# PowerBoard.net
KiCad netlist of a schematic drawn in EAGLE
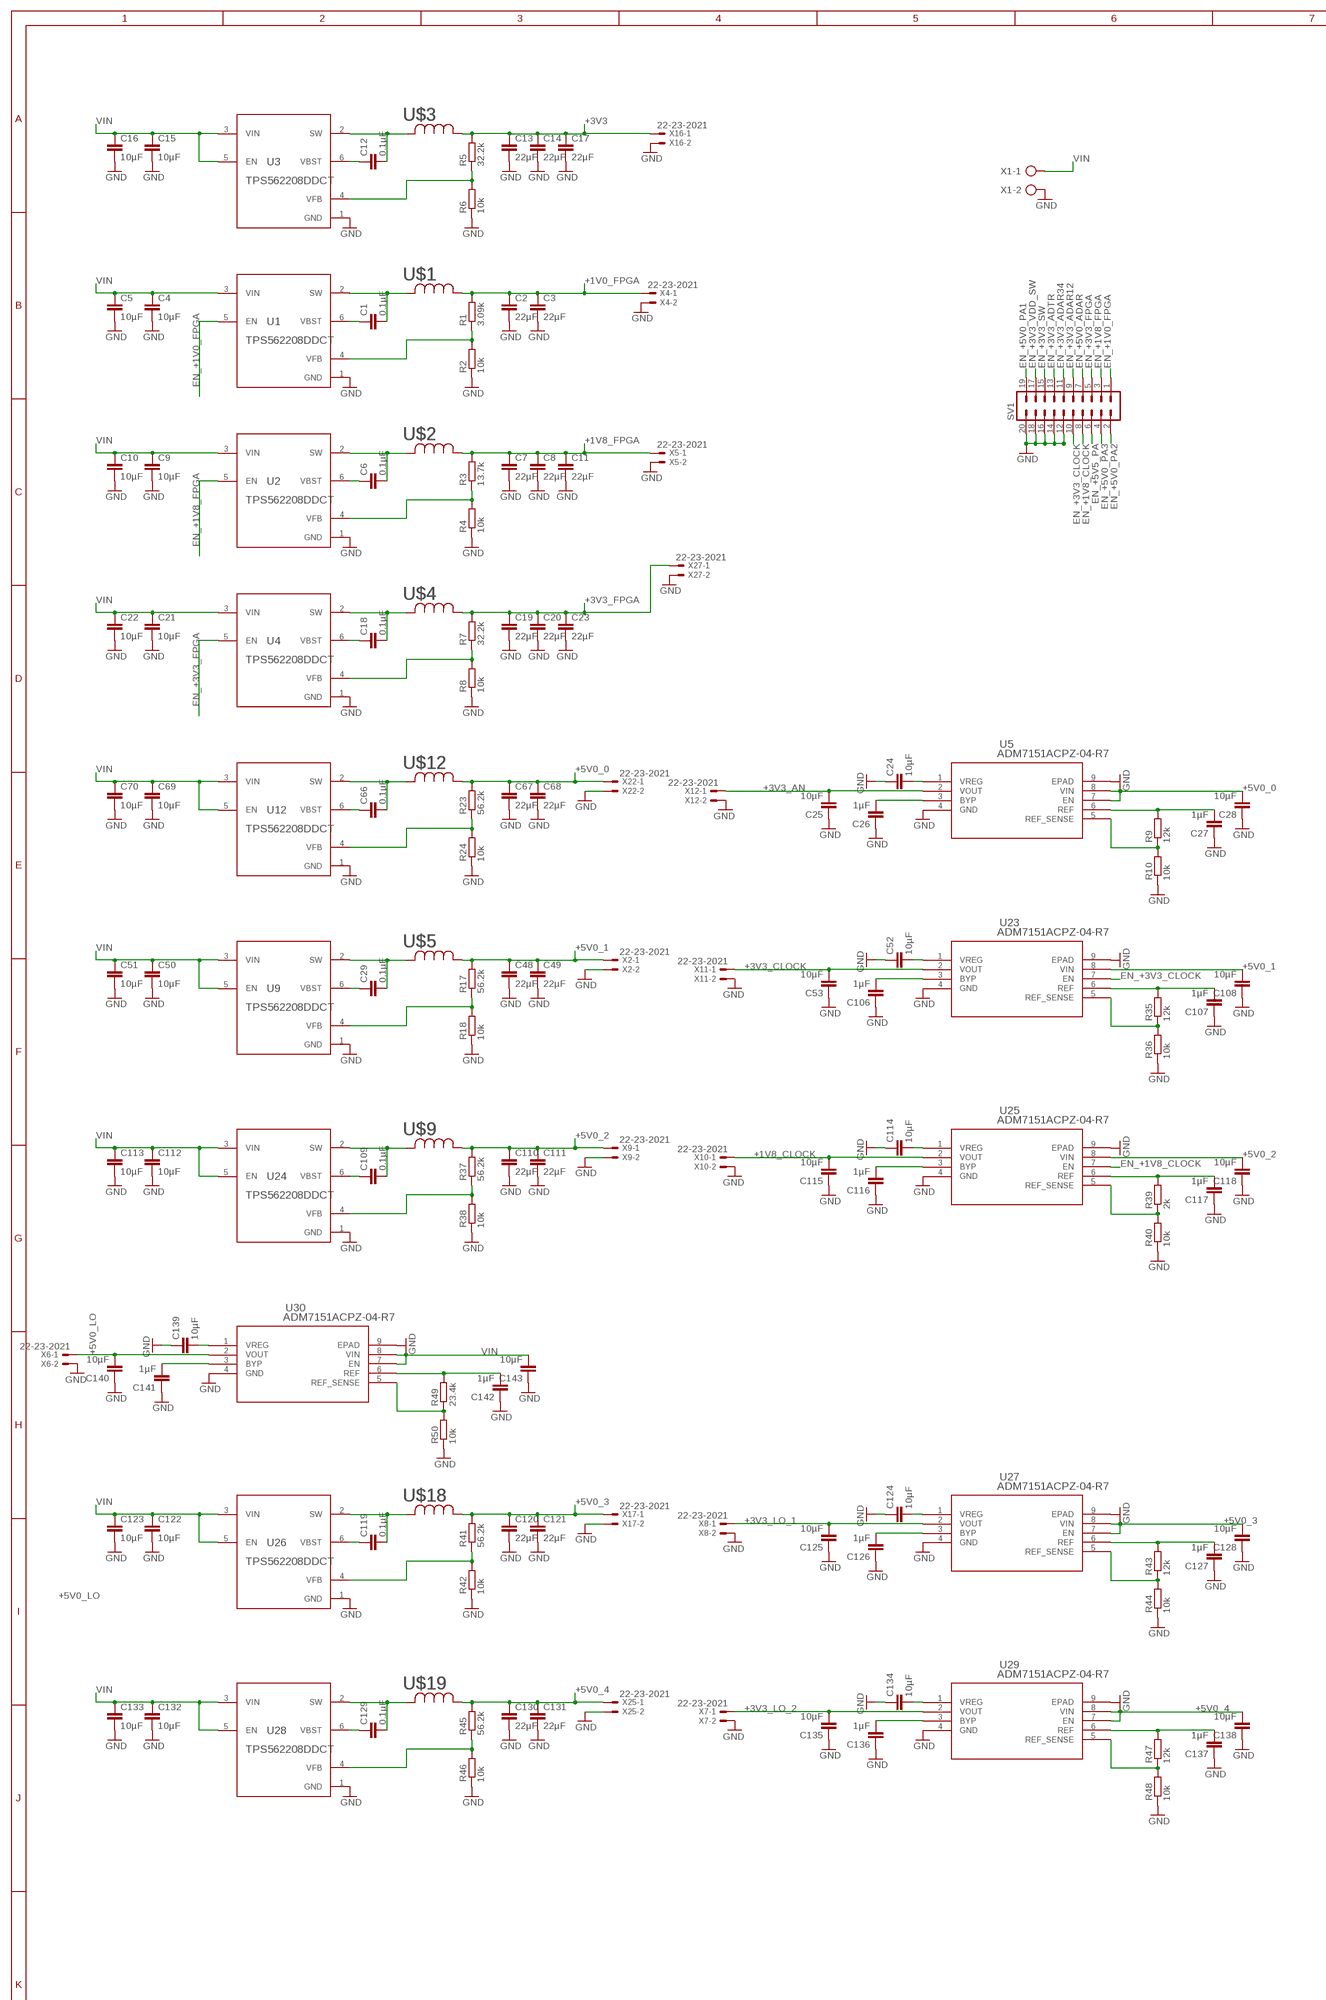
[diagram p0: schematic, sheet 1, part 1 of 3]
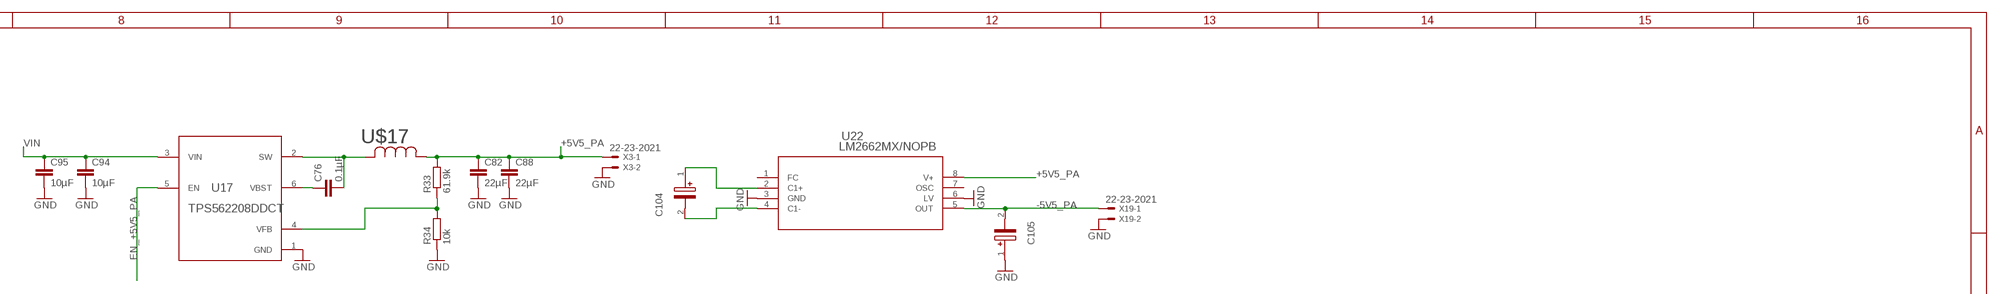
[diagram p1: schematic, sheet 1, part 2 of 3]
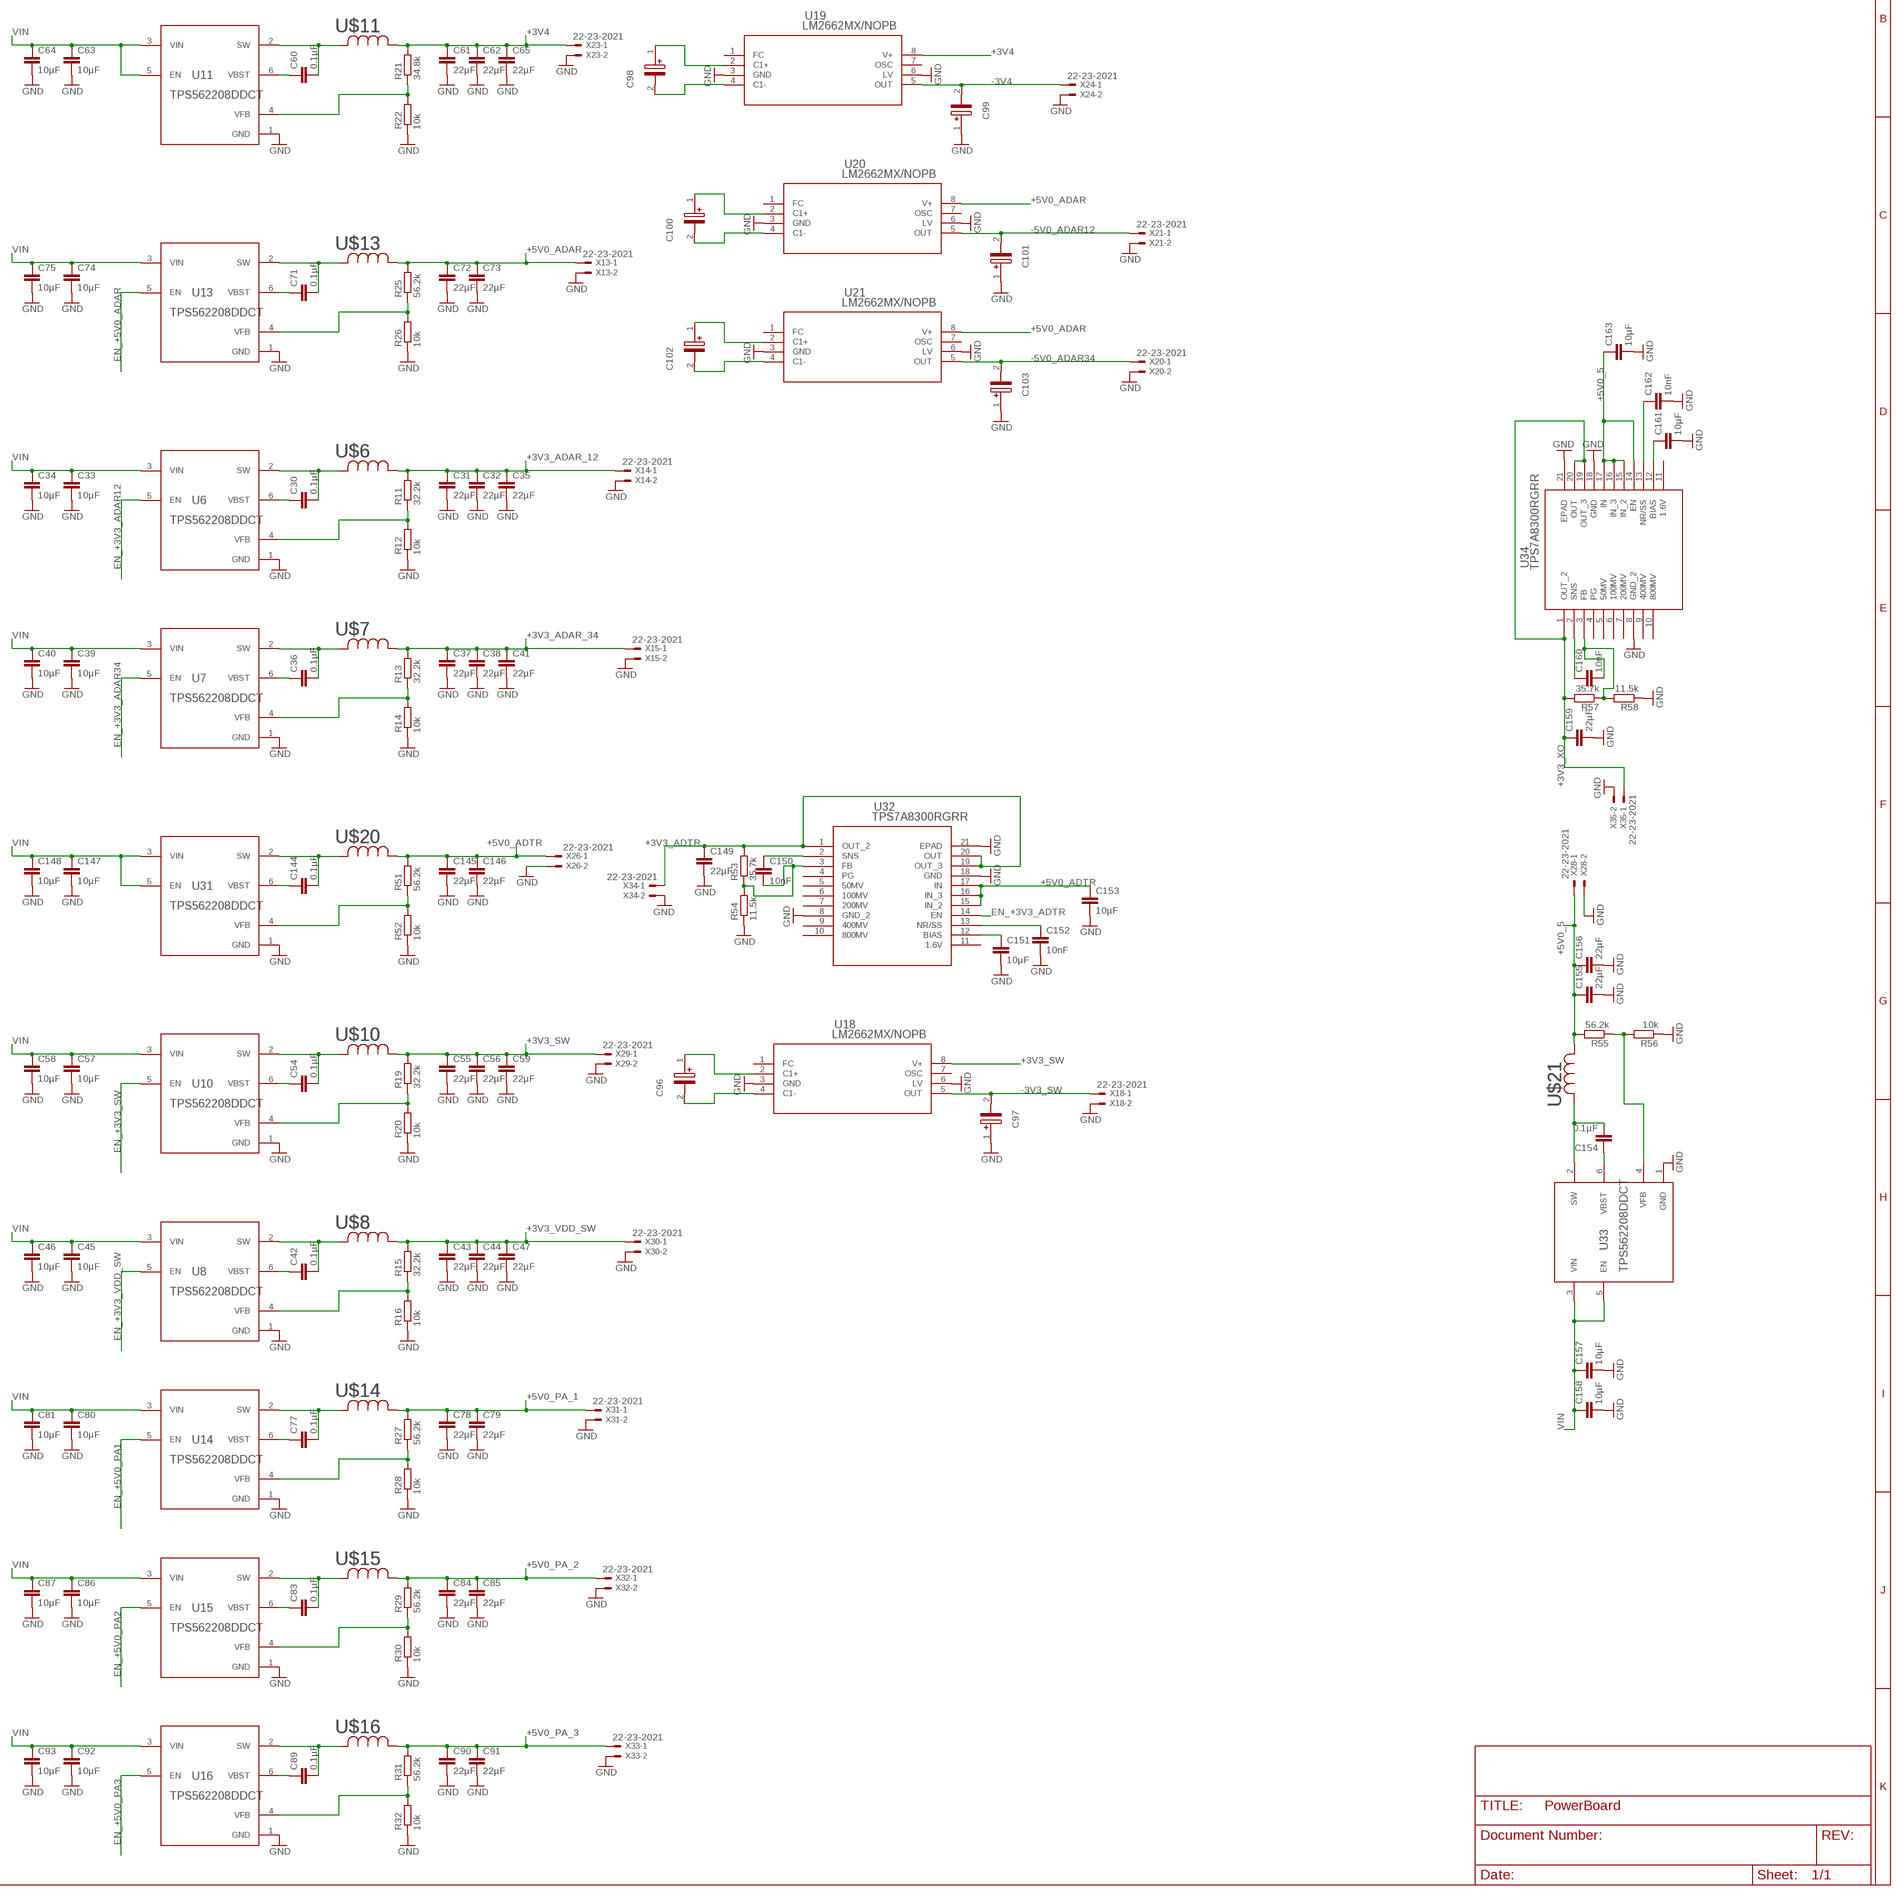
[diagram p2: schematic, sheet 1, part 3 of 3]

(export (version "E")
  (design (tool "Eeschema 10.0.6"))
  (components
    (comp (ref "C1")
      (value "0.1µF")
      (footprint "eagle-import:C0805")
      (libsource (lib "eagle-import") (part "C-EUC0805"))
    )
    (comp (ref "C2")
      (value "22µF")
      (footprint "eagle-import:C0603")
      (libsource (lib "eagle-import") (part "C-EUC0603"))
    )
    (comp (ref "C3")
      (value "22µF")
      (footprint "eagle-import:C0603")
      (libsource (lib "eagle-import") (part "C-EUC0603"))
    )
    (comp (ref "C4")
      (value "10µF")
      (footprint "eagle-import:C0805")
      (libsource (lib "eagle-import") (part "C-EUC0805"))
    )
    (comp (ref "C5")
      (value "10µF")
      (footprint "eagle-import:C0805")
      (libsource (lib "eagle-import") (part "C-EUC0805"))
    )
    (comp (ref "C6")
      (value "0.1µF")
      (footprint "eagle-import:C0805")
      (libsource (lib "eagle-import") (part "C-EUC0805"))
    )
    (comp (ref "C7")
      (value "22µF")
      (footprint "eagle-import:C0603")
      (libsource (lib "eagle-import") (part "C-EUC0603"))
    )
    (comp (ref "C8")
      (value "22µF")
      (footprint "eagle-import:C0603")
      (libsource (lib "eagle-import") (part "C-EUC0603"))
    )
    (comp (ref "C9")
      (value "10µF")
      (footprint "eagle-import:C0805")
      (libsource (lib "eagle-import") (part "C-EUC0805"))
    )
    (comp (ref "C10")
      (value "10µF")
      (footprint "eagle-import:C0805")
      (libsource (lib "eagle-import") (part "C-EUC0805"))
    )
    (comp (ref "C11")
      (value "22µF")
      (footprint "eagle-import:C0603")
      (libsource (lib "eagle-import") (part "C-EUC0603"))
    )
    (comp (ref "C12")
      (value "0.1µF")
      (footprint "eagle-import:C0805")
      (libsource (lib "eagle-import") (part "C-EUC0805"))
    )
    (comp (ref "C13")
      (value "22µF")
      (footprint "eagle-import:C0603")
      (libsource (lib "eagle-import") (part "C-EUC0603"))
    )
    (comp (ref "C14")
      (value "22µF")
      (footprint "eagle-import:C0603")
      (libsource (lib "eagle-import") (part "C-EUC0603"))
    )
    (comp (ref "C15")
      (value "10µF")
      (footprint "eagle-import:C0805")
      (libsource (lib "eagle-import") (part "C-EUC0805"))
    )
    (comp (ref "C16")
      (value "10µF")
      (footprint "eagle-import:C0805")
      (libsource (lib "eagle-import") (part "C-EUC0805"))
    )
    (comp (ref "C17")
      (value "22µF")
      (footprint "eagle-import:C0603")
      (libsource (lib "eagle-import") (part "C-EUC0603"))
    )
    (comp (ref "C18")
      (value "0.1µF")
      (footprint "eagle-import:C0805")
      (libsource (lib "eagle-import") (part "C-EUC0805"))
    )
    (comp (ref "C19")
      (value "22µF")
      (footprint "eagle-import:C0603")
      (libsource (lib "eagle-import") (part "C-EUC0603"))
    )
    (comp (ref "C20")
      (value "22µF")
      (footprint "eagle-import:C0603")
      (libsource (lib "eagle-import") (part "C-EUC0603"))
    )
    (comp (ref "C21")
      (value "10µF")
      (footprint "eagle-import:C0805")
      (libsource (lib "eagle-import") (part "C-EUC0805"))
    )
    (comp (ref "C22")
      (value "10µF")
      (footprint "eagle-import:C0805")
      (libsource (lib "eagle-import") (part "C-EUC0805"))
    )
    (comp (ref "C23")
      (value "22µF")
      (footprint "eagle-import:C0603")
      (libsource (lib "eagle-import") (part "C-EUC0603"))
    )
    (comp (ref "C24")
      (value "10µF")
      (footprint "eagle-import:C0805")
      (libsource (lib "eagle-import") (part "C-EUC0805"))
    )
    (comp (ref "C25")
      (value "10µF")
      (footprint "eagle-import:C0805")
      (libsource (lib "eagle-import") (part "C-EUC0805"))
    )
    (comp (ref "C26")
      (value "1µF")
      (footprint "eagle-import:C0805")
      (libsource (lib "eagle-import") (part "C-EUC0805"))
    )
    (comp (ref "C27")
      (value "1µF")
      (footprint "eagle-import:C0805")
      (libsource (lib "eagle-import") (part "C-EUC0805"))
    )
    (comp (ref "C28")
      (value "10µF")
      (footprint "eagle-import:C0805")
      (libsource (lib "eagle-import") (part "C-EUC0805"))
    )
    (comp (ref "C29")
      (value "0.1µF")
      (footprint "eagle-import:C0805")
      (libsource (lib "eagle-import") (part "C-EUC0805"))
    )
    (comp (ref "C30")
      (value "0.1µF")
      (footprint "eagle-import:C0805")
      (libsource (lib "eagle-import") (part "C-EUC0805"))
    )
    (comp (ref "C31")
      (value "22µF")
      (footprint "eagle-import:C0603")
      (libsource (lib "eagle-import") (part "C-EUC0603"))
    )
    (comp (ref "C32")
      (value "22µF")
      (footprint "eagle-import:C0603")
      (libsource (lib "eagle-import") (part "C-EUC0603"))
    )
    (comp (ref "C33")
      (value "10µF")
      (footprint "eagle-import:C0805")
      (libsource (lib "eagle-import") (part "C-EUC0805"))
    )
    (comp (ref "C34")
      (value "10µF")
      (footprint "eagle-import:C0805")
      (libsource (lib "eagle-import") (part "C-EUC0805"))
    )
    (comp (ref "C35")
      (value "22µF")
      (footprint "eagle-import:C0603")
      (libsource (lib "eagle-import") (part "C-EUC0603"))
    )
    (comp (ref "C36")
      (value "0.1µF")
      (footprint "eagle-import:C0805")
      (libsource (lib "eagle-import") (part "C-EUC0805"))
    )
    (comp (ref "C37")
      (value "22µF")
      (footprint "eagle-import:C0603")
      (libsource (lib "eagle-import") (part "C-EUC0603"))
    )
    (comp (ref "C38")
      (value "22µF")
      (footprint "eagle-import:C0603")
      (libsource (lib "eagle-import") (part "C-EUC0603"))
    )
    (comp (ref "C39")
      (value "10µF")
      (footprint "eagle-import:C0805")
      (libsource (lib "eagle-import") (part "C-EUC0805"))
    )
    (comp (ref "C40")
      (value "10µF")
      (footprint "eagle-import:C0805")
      (libsource (lib "eagle-import") (part "C-EUC0805"))
    )
    (comp (ref "C41")
      (value "22µF")
      (footprint "eagle-import:C0603")
      (libsource (lib "eagle-import") (part "C-EUC0603"))
    )
    (comp (ref "C42")
      (value "0.1µF")
      (footprint "eagle-import:C0805")
      (libsource (lib "eagle-import") (part "C-EUC0805"))
    )
    (comp (ref "C43")
      (value "22µF")
      (footprint "eagle-import:C0603")
      (libsource (lib "eagle-import") (part "C-EUC0603"))
    )
    (comp (ref "C44")
      (value "22µF")
      (footprint "eagle-import:C0603")
      (libsource (lib "eagle-import") (part "C-EUC0603"))
    )
    (comp (ref "C45")
      (value "10µF")
      (footprint "eagle-import:C0805")
      (libsource (lib "eagle-import") (part "C-EUC0805"))
    )
    (comp (ref "C46")
      (value "10µF")
      (footprint "eagle-import:C0805")
      (libsource (lib "eagle-import") (part "C-EUC0805"))
    )
    (comp (ref "C47")
      (value "22µF")
      (footprint "eagle-import:C0603")
      (libsource (lib "eagle-import") (part "C-EUC0603"))
    )
    (comp (ref "C48")
      (value "22µF")
      (footprint "eagle-import:C0603")
      (libsource (lib "eagle-import") (part "C-EUC0603"))
    )
    (comp (ref "C49")
      (value "22µF")
      (footprint "eagle-import:C0603")
      (libsource (lib "eagle-import") (part "C-EUC0603"))
    )
    (comp (ref "C50")
      (value "10µF")
      (footprint "eagle-import:C0805")
      (libsource (lib "eagle-import") (part "C-EUC0805"))
    )
    (comp (ref "C51")
      (value "10µF")
      (footprint "eagle-import:C0805")
      (libsource (lib "eagle-import") (part "C-EUC0805"))
    )
    (comp (ref "C52")
      (value "10µF")
      (footprint "eagle-import:C0805")
      (libsource (lib "eagle-import") (part "C-EUC0805"))
    )
    (comp (ref "C53")
      (value "10µF")
      (footprint "eagle-import:C0805")
      (libsource (lib "eagle-import") (part "C-EUC0805"))
    )
    (comp (ref "C54")
      (value "0.1µF")
      (footprint "eagle-import:C0805")
      (libsource (lib "eagle-import") (part "C-EUC0805"))
    )
    (comp (ref "C55")
      (value "22µF")
      (footprint "eagle-import:C0603")
      (libsource (lib "eagle-import") (part "C-EUC0603"))
    )
    (comp (ref "C56")
      (value "22µF")
      (footprint "eagle-import:C0603")
      (libsource (lib "eagle-import") (part "C-EUC0603"))
    )
    (comp (ref "C57")
      (value "10µF")
      (footprint "eagle-import:C0805")
      (libsource (lib "eagle-import") (part "C-EUC0805"))
    )
    (comp (ref "C58")
      (value "10µF")
      (footprint "eagle-import:C0805")
      (libsource (lib "eagle-import") (part "C-EUC0805"))
    )
    (comp (ref "C59")
      (value "22µF")
      (footprint "eagle-import:C0603")
      (libsource (lib "eagle-import") (part "C-EUC0603"))
    )
    (comp (ref "C60")
      (value "0.1µF")
      (footprint "eagle-import:C0805")
      (libsource (lib "eagle-import") (part "C-EUC0805"))
    )
    (comp (ref "C61")
      (value "22µF")
      (footprint "eagle-import:C0603")
      (libsource (lib "eagle-import") (part "C-EUC0603"))
    )
    (comp (ref "C62")
      (value "22µF")
      (footprint "eagle-import:C0603")
      (libsource (lib "eagle-import") (part "C-EUC0603"))
    )
    (comp (ref "C63")
      (value "10µF")
      (footprint "eagle-import:C0805")
      (libsource (lib "eagle-import") (part "C-EUC0805"))
    )
    (comp (ref "C64")
      (value "10µF")
      (footprint "eagle-import:C0805")
      (libsource (lib "eagle-import") (part "C-EUC0805"))
    )
    (comp (ref "C65")
      (value "22µF")
      (footprint "eagle-import:C0603")
      (libsource (lib "eagle-import") (part "C-EUC0603"))
    )
    (comp (ref "C66")
      (value "0.1µF")
      (footprint "eagle-import:C0805")
      (libsource (lib "eagle-import") (part "C-EUC0805"))
    )
    (comp (ref "C67")
      (value "22µF")
      (footprint "eagle-import:C0603")
      (libsource (lib "eagle-import") (part "C-EUC0603"))
    )
    (comp (ref "C68")
      (value "22µF")
      (footprint "eagle-import:C0603")
      (libsource (lib "eagle-import") (part "C-EUC0603"))
    )
    (comp (ref "C69")
      (value "10µF")
      (footprint "eagle-import:C0805")
      (libsource (lib "eagle-import") (part "C-EUC0805"))
    )
    (comp (ref "C70")
      (value "10µF")
      (footprint "eagle-import:C0805")
      (libsource (lib "eagle-import") (part "C-EUC0805"))
    )
    (comp (ref "C71")
      (value "0.1µF")
      (footprint "eagle-import:C0805")
      (libsource (lib "eagle-import") (part "C-EUC0805"))
    )
    (comp (ref "C72")
      (value "22µF")
      (footprint "eagle-import:C0603")
      (libsource (lib "eagle-import") (part "C-EUC0603"))
    )
    (comp (ref "C73")
      (value "22µF")
      (footprint "eagle-import:C0603")
      (libsource (lib "eagle-import") (part "C-EUC0603"))
    )
    (comp (ref "C74")
      (value "10µF")
      (footprint "eagle-import:C0805")
      (libsource (lib "eagle-import") (part "C-EUC0805"))
    )
    (comp (ref "C75")
      (value "10µF")
      (footprint "eagle-import:C0805")
      (libsource (lib "eagle-import") (part "C-EUC0805"))
    )
    (comp (ref "C76")
      (value "0.1µF")
      (footprint "eagle-import:C0805")
      (libsource (lib "eagle-import") (part "C-EUC0805"))
    )
    (comp (ref "C77")
      (value "0.1µF")
      (footprint "eagle-import:C0805")
      (libsource (lib "eagle-import") (part "C-EUC0805"))
    )
    (comp (ref "C78")
      (value "22µF")
      (footprint "eagle-import:C0603")
      (libsource (lib "eagle-import") (part "C-EUC0603"))
    )
    (comp (ref "C79")
      (value "22µF")
      (footprint "eagle-import:C0603")
      (libsource (lib "eagle-import") (part "C-EUC0603"))
    )
    (comp (ref "C80")
      (value "10µF")
      (footprint "eagle-import:C0805")
      (libsource (lib "eagle-import") (part "C-EUC0805"))
    )
    (comp (ref "C81")
      (value "10µF")
      (footprint "eagle-import:C0805")
      (libsource (lib "eagle-import") (part "C-EUC0805"))
    )
    (comp (ref "C82")
      (value "22µF")
      (footprint "eagle-import:C0603")
      (libsource (lib "eagle-import") (part "C-EUC0603"))
    )
    (comp (ref "C83")
      (value "0.1µF")
      (footprint "eagle-import:C0805")
      (libsource (lib "eagle-import") (part "C-EUC0805"))
    )
    (comp (ref "C84")
      (value "22µF")
      (footprint "eagle-import:C0603")
      (libsource (lib "eagle-import") (part "C-EUC0603"))
    )
    (comp (ref "C85")
      (value "22µF")
      (footprint "eagle-import:C0603")
      (libsource (lib "eagle-import") (part "C-EUC0603"))
    )
    (comp (ref "C86")
      (value "10µF")
      (footprint "eagle-import:C0805")
      (libsource (lib "eagle-import") (part "C-EUC0805"))
    )
    (comp (ref "C87")
      (value "10µF")
      (footprint "eagle-import:C0805")
      (libsource (lib "eagle-import") (part "C-EUC0805"))
    )
    (comp (ref "C88")
      (value "22µF")
      (footprint "eagle-import:C0603")
      (libsource (lib "eagle-import") (part "C-EUC0603"))
    )
    (comp (ref "C89")
      (value "0.1µF")
      (footprint "eagle-import:C0805")
      (libsource (lib "eagle-import") (part "C-EUC0805"))
    )
    (comp (ref "C90")
      (value "22µF")
      (footprint "eagle-import:C0603")
      (libsource (lib "eagle-import") (part "C-EUC0603"))
    )
    (comp (ref "C91")
      (value "22µF")
      (footprint "eagle-import:C0603")
      (libsource (lib "eagle-import") (part "C-EUC0603"))
    )
    (comp (ref "C92")
      (value "10µF")
      (footprint "eagle-import:C0805")
      (libsource (lib "eagle-import") (part "C-EUC0805"))
    )
    (comp (ref "C93")
      (value "10µF")
      (footprint "eagle-import:C0805")
      (libsource (lib "eagle-import") (part "C-EUC0805"))
    )
    (comp (ref "C94")
      (value "10µF")
      (footprint "eagle-import:C0805")
      (libsource (lib "eagle-import") (part "C-EUC0805"))
    )
    (comp (ref "C95")
      (value "10µF")
      (footprint "eagle-import:C0805")
      (libsource (lib "eagle-import") (part "C-EUC0805"))
    )
    (comp (ref "C96")
      (value "T521W476M020ATE045")
      (footprint "eagle-import:T521W")
      (fields (field (name "MOUSER_PART_NUMBER") "80-T521W476M20ATE045"))
      (libsource (lib "eagle-import") (part "T521W476M020ATE045"))
    )
    (comp (ref "C97")
      (value "T521W476M020ATE045")
      (footprint "eagle-import:T521W")
      (fields (field (name "MOUSER_PART_NUMBER") "80-T521W476M20ATE045"))
      (libsource (lib "eagle-import") (part "T521W476M020ATE045"))
    )
    (comp (ref "C98")
      (value "T521W476M020ATE045")
      (footprint "eagle-import:T521W")
      (fields (field (name "MOUSER_PART_NUMBER") "80-T521W476M20ATE045"))
      (libsource (lib "eagle-import") (part "T521W476M020ATE045"))
    )
    (comp (ref "C99")
      (value "T521W476M020ATE045")
      (footprint "eagle-import:T521W")
      (fields (field (name "MOUSER_PART_NUMBER") "80-T521W476M20ATE045"))
      (libsource (lib "eagle-import") (part "T521W476M020ATE045"))
    )
    (comp (ref "C100")
      (value "T521W476M020ATE045")
      (footprint "eagle-import:T521W")
      (fields (field (name "MOUSER_PART_NUMBER") "80-T521W476M20ATE045"))
      (libsource (lib "eagle-import") (part "T521W476M020ATE045"))
    )
    (comp (ref "C101")
      (value "T521W476M020ATE045")
      (footprint "eagle-import:T521W")
      (fields (field (name "MOUSER_PART_NUMBER") "80-T521W476M20ATE045"))
      (libsource (lib "eagle-import") (part "T521W476M020ATE045"))
    )
    (comp (ref "C102")
      (value "T521W476M020ATE045")
      (footprint "eagle-import:T521W")
      (fields (field (name "MOUSER_PART_NUMBER") "80-T521W476M20ATE045"))
      (libsource (lib "eagle-import") (part "T521W476M020ATE045"))
    )
    (comp (ref "C103")
      (value "T521W476M020ATE045")
      (footprint "eagle-import:T521W")
      (fields (field (name "MOUSER_PART_NUMBER") "80-T521W476M20ATE045"))
      (libsource (lib "eagle-import") (part "T521W476M020ATE045"))
    )
    (comp (ref "C104")
      (value "T521W476M020ATE045")
      (footprint "eagle-import:T521W")
      (fields (field (name "MOUSER_PART_NUMBER") "80-T521W476M20ATE045"))
      (libsource (lib "eagle-import") (part "T521W476M020ATE045"))
    )
    (comp (ref "C105")
      (value "T521W476M020ATE045")
      (footprint "eagle-import:T521W")
      (fields (field (name "MOUSER_PART_NUMBER") "80-T521W476M20ATE045"))
      (libsource (lib "eagle-import") (part "T521W476M020ATE045"))
    )
    (comp (ref "C106")
      (value "1µF")
      (footprint "eagle-import:C0805")
      (libsource (lib "eagle-import") (part "C-EUC0805"))
    )
    (comp (ref "C107")
      (value "1µF")
      (footprint "eagle-import:C0805")
      (libsource (lib "eagle-import") (part "C-EUC0805"))
    )
    (comp (ref "C108")
      (value "10µF")
      (footprint "eagle-import:C0805")
      (libsource (lib "eagle-import") (part "C-EUC0805"))
    )
    (comp (ref "C109")
      (value "0.1µF")
      (footprint "eagle-import:C0805")
      (libsource (lib "eagle-import") (part "C-EUC0805"))
    )
    (comp (ref "C110")
      (value "22µF")
      (footprint "eagle-import:C0603")
      (libsource (lib "eagle-import") (part "C-EUC0603"))
    )
    (comp (ref "C111")
      (value "22µF")
      (footprint "eagle-import:C0603")
      (libsource (lib "eagle-import") (part "C-EUC0603"))
    )
    (comp (ref "C112")
      (value "10µF")
      (footprint "eagle-import:C0805")
      (libsource (lib "eagle-import") (part "C-EUC0805"))
    )
    (comp (ref "C113")
      (value "10µF")
      (footprint "eagle-import:C0805")
      (libsource (lib "eagle-import") (part "C-EUC0805"))
    )
    (comp (ref "C114")
      (value "10µF")
      (footprint "eagle-import:C0805")
      (libsource (lib "eagle-import") (part "C-EUC0805"))
    )
    (comp (ref "C115")
      (value "10µF")
      (footprint "eagle-import:C0805")
      (libsource (lib "eagle-import") (part "C-EUC0805"))
    )
    (comp (ref "C116")
      (value "1µF")
      (footprint "eagle-import:C0805")
      (libsource (lib "eagle-import") (part "C-EUC0805"))
    )
    (comp (ref "C117")
      (value "1µF")
      (footprint "eagle-import:C0805")
      (libsource (lib "eagle-import") (part "C-EUC0805"))
    )
    (comp (ref "C118")
      (value "10µF")
      (footprint "eagle-import:C0805")
      (libsource (lib "eagle-import") (part "C-EUC0805"))
    )
    (comp (ref "C119")
      (value "0.1µF")
      (footprint "eagle-import:C0805")
      (libsource (lib "eagle-import") (part "C-EUC0805"))
    )
    (comp (ref "C120")
      (value "22µF")
      (footprint "eagle-import:C0603")
      (libsource (lib "eagle-import") (part "C-EUC0603"))
    )
    (comp (ref "C121")
      (value "22µF")
      (footprint "eagle-import:C0603")
      (libsource (lib "eagle-import") (part "C-EUC0603"))
    )
    (comp (ref "C122")
      (value "10µF")
      (footprint "eagle-import:C0805")
      (libsource (lib "eagle-import") (part "C-EUC0805"))
    )
    (comp (ref "C123")
      (value "10µF")
      (footprint "eagle-import:C0805")
      (libsource (lib "eagle-import") (part "C-EUC0805"))
    )
    (comp (ref "C124")
      (value "10µF")
      (footprint "eagle-import:C0805")
      (libsource (lib "eagle-import") (part "C-EUC0805"))
    )
    (comp (ref "C125")
      (value "10µF")
      (footprint "eagle-import:C0805")
      (libsource (lib "eagle-import") (part "C-EUC0805"))
    )
    (comp (ref "C126")
      (value "1µF")
      (footprint "eagle-import:C0805")
      (libsource (lib "eagle-import") (part "C-EUC0805"))
    )
    (comp (ref "C127")
      (value "1µF")
      (footprint "eagle-import:C0805")
      (libsource (lib "eagle-import") (part "C-EUC0805"))
    )
    (comp (ref "C128")
      (value "10µF")
      (footprint "eagle-import:C0805")
      (libsource (lib "eagle-import") (part "C-EUC0805"))
    )
    (comp (ref "C129")
      (value "0.1µF")
      (footprint "eagle-import:C0805")
      (libsource (lib "eagle-import") (part "C-EUC0805"))
    )
    (comp (ref "C130")
      (value "22µF")
      (footprint "eagle-import:C0603")
      (libsource (lib "eagle-import") (part "C-EUC0603"))
    )
    (comp (ref "C131")
      (value "22µF")
      (footprint "eagle-import:C0603")
      (libsource (lib "eagle-import") (part "C-EUC0603"))
    )
    (comp (ref "C132")
      (value "10µF")
      (footprint "eagle-import:C0805")
      (libsource (lib "eagle-import") (part "C-EUC0805"))
    )
    (comp (ref "C133")
      (value "10µF")
      (footprint "eagle-import:C0805")
      (libsource (lib "eagle-import") (part "C-EUC0805"))
    )
    (comp (ref "C134")
      (value "10µF")
      (footprint "eagle-import:C0805")
      (libsource (lib "eagle-import") (part "C-EUC0805"))
    )
    (comp (ref "C135")
      (value "10µF")
      (footprint "eagle-import:C0805")
      (libsource (lib "eagle-import") (part "C-EUC0805"))
    )
    (comp (ref "C136")
      (value "1µF")
      (footprint "eagle-import:C0805")
      (libsource (lib "eagle-import") (part "C-EUC0805"))
    )
    (comp (ref "C137")
      (value "1µF")
      (footprint "eagle-import:C0805")
      (libsource (lib "eagle-import") (part "C-EUC0805"))
    )
    (comp (ref "C138")
      (value "10µF")
      (footprint "eagle-import:C0805")
      (libsource (lib "eagle-import") (part "C-EUC0805"))
    )
    (comp (ref "C139")
      (value "10µF")
      (footprint "eagle-import:C0805")
      (libsource (lib "eagle-import") (part "C-EUC0805"))
    )
    (comp (ref "C140")
      (value "10µF")
      (footprint "eagle-import:C0805")
      (libsource (lib "eagle-import") (part "C-EUC0805"))
    )
    (comp (ref "C141")
      (value "1µF")
      (footprint "eagle-import:C0805")
      (libsource (lib "eagle-import") (part "C-EUC0805"))
    )
    (comp (ref "C142")
      (value "1µF")
      (footprint "eagle-import:C0805")
      (libsource (lib "eagle-import") (part "C-EUC0805"))
    )
    (comp (ref "C143")
      (value "10µF")
      (footprint "eagle-import:C0805")
      (libsource (lib "eagle-import") (part "C-EUC0805"))
    )
    (comp (ref "C144")
      (value "0.1µF")
      (footprint "eagle-import:C0805")
      (libsource (lib "eagle-import") (part "C-EUC0805"))
    )
    (comp (ref "C145")
      (value "22µF")
      (footprint "eagle-import:C0603")
      (libsource (lib "eagle-import") (part "C-EUC0603"))
    )
    (comp (ref "C146")
      (value "22µF")
      (footprint "eagle-import:C0603")
      (libsource (lib "eagle-import") (part "C-EUC0603"))
    )
    (comp (ref "C147")
      (value "10µF")
      (footprint "eagle-import:C0805")
      (libsource (lib "eagle-import") (part "C-EUC0805"))
    )
    (comp (ref "C148")
      (value "10µF")
      (footprint "eagle-import:C0805")
      (libsource (lib "eagle-import") (part "C-EUC0805"))
    )
    (comp (ref "C149")
      (value "22µF")
      (footprint "eagle-import:C0603")
      (libsource (lib "eagle-import") (part "C-EUC0603"))
    )
    (comp (ref "C150")
      (value "10nF")
      (footprint "eagle-import:C0603")
      (libsource (lib "eagle-import") (part "C-EUC0603"))
    )
    (comp (ref "C151")
      (value "10µF")
      (footprint "eagle-import:C0603")
      (libsource (lib "eagle-import") (part "C-EUC0603"))
    )
    (comp (ref "C152")
      (value "10nF")
      (footprint "eagle-import:C0603")
      (libsource (lib "eagle-import") (part "C-EUC0603"))
    )
    (comp (ref "C153")
      (value "10µF")
      (footprint "eagle-import:C0603")
      (libsource (lib "eagle-import") (part "C-EUC0603"))
    )
    (comp (ref "C154")
      (value "0.1µF")
      (footprint "eagle-import:C0805")
      (libsource (lib "eagle-import") (part "C-EUC0805"))
    )
    (comp (ref "C155")
      (value "22µF")
      (footprint "eagle-import:C0603")
      (libsource (lib "eagle-import") (part "C-EUC0603"))
    )
    (comp (ref "C156")
      (value "22µF")
      (footprint "eagle-import:C0603")
      (libsource (lib "eagle-import") (part "C-EUC0603"))
    )
    (comp (ref "C157")
      (value "10µF")
      (footprint "eagle-import:C0805")
      (libsource (lib "eagle-import") (part "C-EUC0805"))
    )
    (comp (ref "C158")
      (value "10µF")
      (footprint "eagle-import:C0805")
      (libsource (lib "eagle-import") (part "C-EUC0805"))
    )
    (comp (ref "C159")
      (value "22µF")
      (footprint "eagle-import:C0603")
      (libsource (lib "eagle-import") (part "C-EUC0603"))
    )
    (comp (ref "C160")
      (value "10nF")
      (footprint "eagle-import:C0603")
      (libsource (lib "eagle-import") (part "C-EUC0603"))
    )
    (comp (ref "C161")
      (value "10µF")
      (footprint "eagle-import:C0603")
      (libsource (lib "eagle-import") (part "C-EUC0603"))
    )
    (comp (ref "C162")
      (value "10nF")
      (footprint "eagle-import:C0603")
      (libsource (lib "eagle-import") (part "C-EUC0603"))
    )
    (comp (ref "C163")
      (value "10µF")
      (footprint "eagle-import:C0603")
      (libsource (lib "eagle-import") (part "C-EUC0603"))
    )
    (comp (ref "R1")
      (value "3.09k")
      (footprint "eagle-import:M0805")
      (libsource (lib "eagle-import") (part "R-EU_M0805"))
    )
    (comp (ref "R2")
      (value "10k")
      (footprint "eagle-import:M0805")
      (libsource (lib "eagle-import") (part "R-EU_M0805"))
    )
    (comp (ref "R3")
      (value "13.7k")
      (footprint "eagle-import:M0805")
      (libsource (lib "eagle-import") (part "R-EU_M0805"))
    )
    (comp (ref "R4")
      (value "10k")
      (footprint "eagle-import:M0805")
      (libsource (lib "eagle-import") (part "R-EU_M0805"))
    )
    (comp (ref "R5")
      (value "32.2k")
      (footprint "eagle-import:M0805")
      (libsource (lib "eagle-import") (part "R-EU_M0805"))
    )
    (comp (ref "R6")
      (value "10k")
      (footprint "eagle-import:M0805")
      (libsource (lib "eagle-import") (part "R-EU_M0805"))
    )
    (comp (ref "R7")
      (value "32.2k")
      (footprint "eagle-import:M0805")
      (libsource (lib "eagle-import") (part "R-EU_M0805"))
    )
    (comp (ref "R8")
      (value "10k")
      (footprint "eagle-import:M0805")
      (libsource (lib "eagle-import") (part "R-EU_M0805"))
    )
    (comp (ref "R9")
      (value "12k")
      (footprint "eagle-import:M0805")
      (libsource (lib "eagle-import") (part "R-EU_M0805"))
    )
    (comp (ref "R10")
      (value "10k")
      (footprint "eagle-import:M0805")
      (libsource (lib "eagle-import") (part "R-EU_M0805"))
    )
    (comp (ref "R11")
      (value "32.2k")
      (footprint "eagle-import:M0805")
      (libsource (lib "eagle-import") (part "R-EU_M0805"))
    )
    (comp (ref "R12")
      (value "10k")
      (footprint "eagle-import:M0805")
      (libsource (lib "eagle-import") (part "R-EU_M0805"))
    )
    (comp (ref "R13")
      (value "32.2k")
      (footprint "eagle-import:M0805")
      (libsource (lib "eagle-import") (part "R-EU_M0805"))
    )
    (comp (ref "R14")
      (value "10k")
      (footprint "eagle-import:M0805")
      (libsource (lib "eagle-import") (part "R-EU_M0805"))
    )
    (comp (ref "R15")
      (value "32.2k")
      (footprint "eagle-import:M0805")
      (libsource (lib "eagle-import") (part "R-EU_M0805"))
    )
    (comp (ref "R16")
      (value "10k")
      (footprint "eagle-import:M0805")
      (libsource (lib "eagle-import") (part "R-EU_M0805"))
    )
    (comp (ref "R17")
      (value "56.2k")
      (footprint "eagle-import:M0805")
      (libsource (lib "eagle-import") (part "R-EU_M0805"))
    )
    (comp (ref "R18")
      (value "10k")
      (footprint "eagle-import:M0805")
      (libsource (lib "eagle-import") (part "R-EU_M0805"))
    )
    (comp (ref "R19")
      (value "32.2k")
      (footprint "eagle-import:M0805")
      (libsource (lib "eagle-import") (part "R-EU_M0805"))
    )
    (comp (ref "R20")
      (value "10k")
      (footprint "eagle-import:M0805")
      (libsource (lib "eagle-import") (part "R-EU_M0805"))
    )
    (comp (ref "R21")
      (value "34.8k")
      (footprint "eagle-import:M0805")
      (libsource (lib "eagle-import") (part "R-EU_M0805"))
    )
    (comp (ref "R22")
      (value "10k")
      (footprint "eagle-import:M0805")
      (libsource (lib "eagle-import") (part "R-EU_M0805"))
    )
    (comp (ref "R23")
      (value "56.2k")
      (footprint "eagle-import:M0805")
      (libsource (lib "eagle-import") (part "R-EU_M0805"))
    )
    (comp (ref "R24")
      (value "10k")
      (footprint "eagle-import:M0805")
      (libsource (lib "eagle-import") (part "R-EU_M0805"))
    )
    (comp (ref "R25")
      (value "56.2k")
      (footprint "eagle-import:M0805")
      (libsource (lib "eagle-import") (part "R-EU_M0805"))
    )
    (comp (ref "R26")
      (value "10k")
      (footprint "eagle-import:M0805")
      (libsource (lib "eagle-import") (part "R-EU_M0805"))
    )
    (comp (ref "R27")
      (value "56.2k")
      (footprint "eagle-import:M0805")
      (libsource (lib "eagle-import") (part "R-EU_M0805"))
    )
    (comp (ref "R28")
      (value "10k")
      (footprint "eagle-import:M0805")
      (libsource (lib "eagle-import") (part "R-EU_M0805"))
    )
    (comp (ref "R29")
      (value "56.2k")
      (footprint "eagle-import:M0805")
      (libsource (lib "eagle-import") (part "R-EU_M0805"))
    )
    (comp (ref "R30")
      (value "10k")
      (footprint "eagle-import:M0805")
      (libsource (lib "eagle-import") (part "R-EU_M0805"))
    )
    (comp (ref "R31")
      (value "56.2k")
      (footprint "eagle-import:M0805")
      (libsource (lib "eagle-import") (part "R-EU_M0805"))
    )
    (comp (ref "R32")
      (value "10k")
      (footprint "eagle-import:M0805")
      (libsource (lib "eagle-import") (part "R-EU_M0805"))
    )
    (comp (ref "R33")
      (value "61.9k")
      (footprint "eagle-import:M0805")
      (libsource (lib "eagle-import") (part "R-EU_M0805"))
    )
    (comp (ref "R34")
      (value "10k")
      (footprint "eagle-import:M0805")
      (libsource (lib "eagle-import") (part "R-EU_M0805"))
    )
    (comp (ref "R35")
      (value "12k")
      (footprint "eagle-import:M0805")
      (libsource (lib "eagle-import") (part "R-EU_M0805"))
    )
    (comp (ref "R36")
      (value "10k")
      (footprint "eagle-import:M0805")
      (libsource (lib "eagle-import") (part "R-EU_M0805"))
    )
    (comp (ref "R37")
      (value "56.2k")
      (footprint "eagle-import:M0805")
      (libsource (lib "eagle-import") (part "R-EU_M0805"))
    )
    (comp (ref "R38")
      (value "10k")
      (footprint "eagle-import:M0805")
      (libsource (lib "eagle-import") (part "R-EU_M0805"))
    )
    (comp (ref "R39")
      (value "2k")
      (footprint "eagle-import:M0805")
      (libsource (lib "eagle-import") (part "R-EU_M0805"))
    )
    (comp (ref "R40")
      (value "10k")
      (footprint "eagle-import:M0805")
      (libsource (lib "eagle-import") (part "R-EU_M0805"))
    )
    (comp (ref "R41")
      (value "56.2k")
      (footprint "eagle-import:M0805")
      (libsource (lib "eagle-import") (part "R-EU_M0805"))
    )
    (comp (ref "R42")
      (value "10k")
      (footprint "eagle-import:M0805")
      (libsource (lib "eagle-import") (part "R-EU_M0805"))
    )
    (comp (ref "R43")
      (value "12k")
      (footprint "eagle-import:M0805")
      (libsource (lib "eagle-import") (part "R-EU_M0805"))
    )
    (comp (ref "R44")
      (value "10k")
      (footprint "eagle-import:M0805")
      (libsource (lib "eagle-import") (part "R-EU_M0805"))
    )
    (comp (ref "R45")
      (value "56.2k")
      (footprint "eagle-import:M0805")
      (libsource (lib "eagle-import") (part "R-EU_M0805"))
    )
    (comp (ref "R46")
      (value "10k")
      (footprint "eagle-import:M0805")
      (libsource (lib "eagle-import") (part "R-EU_M0805"))
    )
    (comp (ref "R47")
      (value "12k")
      (footprint "eagle-import:M0805")
      (libsource (lib "eagle-import") (part "R-EU_M0805"))
    )
    (comp (ref "R48")
      (value "10k")
      (footprint "eagle-import:M0805")
      (libsource (lib "eagle-import") (part "R-EU_M0805"))
    )
    (comp (ref "R49")
      (value "23.4k")
      (footprint "eagle-import:M0805")
      (libsource (lib "eagle-import") (part "R-EU_M0805"))
    )
    (comp (ref "R50")
      (value "10k")
      (footprint "eagle-import:M0805")
      (libsource (lib "eagle-import") (part "R-EU_M0805"))
    )
    (comp (ref "R51")
      (value "56.2k")
      (footprint "eagle-import:M0805")
      (libsource (lib "eagle-import") (part "R-EU_M0805"))
    )
    (comp (ref "R52")
      (value "10k")
      (footprint "eagle-import:M0805")
      (libsource (lib "eagle-import") (part "R-EU_M0805"))
    )
    (comp (ref "R53")
      (value "35.7k")
      (footprint "eagle-import:M0805")
      (libsource (lib "eagle-import") (part "R-EU_M0805"))
    )
    (comp (ref "R54")
      (value "11.5k")
      (footprint "eagle-import:M0805")
      (libsource (lib "eagle-import") (part "R-EU_M0805"))
    )
    (comp (ref "R55")
      (value "56.2k")
      (footprint "eagle-import:M0805")
      (libsource (lib "eagle-import") (part "R-EU_M0805"))
    )
    (comp (ref "R56")
      (value "10k")
      (footprint "eagle-import:M0805")
      (libsource (lib "eagle-import") (part "R-EU_M0805"))
    )
    (comp (ref "R57")
      (value "35.7k")
      (footprint "eagle-import:M0805")
      (libsource (lib "eagle-import") (part "R-EU_M0805"))
    )
    (comp (ref "R58")
      (value "11.5k")
      (footprint "eagle-import:M0805")
      (libsource (lib "eagle-import") (part "R-EU_M0805"))
    )
    (comp (ref "SV1")
      (value "MA10-2")
      (footprint "eagle-import:MA10-2")
      (libsource (lib "eagle-import") (part "MA10-2"))
    )
    (comp (ref "U$1")
      (value "2.2µH")
      (footprint "eagle-import:IND_VLP8040T-1R0N_TDK")
      (libsource (lib "eagle-import") (part "POWER_INDUCTOR"))
    )
    (comp (ref "U$2")
      (value "2.2µH")
      (footprint "eagle-import:IND_VLP8040T-1R0N_TDK")
      (libsource (lib "eagle-import") (part "POWER_INDUCTOR"))
    )
    (comp (ref "U$3")
      (value "3.3µH")
      (footprint "eagle-import:IND_VLP8040T-1R0N_TDK")
      (libsource (lib "eagle-import") (part "POWER_INDUCTOR"))
    )
    (comp (ref "U$4")
      (value "3.3µH")
      (footprint "eagle-import:IND_VLP8040T-1R0N_TDK")
      (libsource (lib "eagle-import") (part "POWER_INDUCTOR"))
    )
    (comp (ref "U$5")
      (value "3.3µH")
      (footprint "eagle-import:IND_VLP8040T-1R0N_TDK")
      (libsource (lib "eagle-import") (part "POWER_INDUCTOR"))
    )
    (comp (ref "U$6")
      (value "3.3µH")
      (footprint "eagle-import:IND_VLP8040T-1R0N_TDK")
      (libsource (lib "eagle-import") (part "POWER_INDUCTOR"))
    )
    (comp (ref "U$7")
      (value "3.3µH")
      (footprint "eagle-import:IND_VLP8040T-1R0N_TDK")
      (libsource (lib "eagle-import") (part "POWER_INDUCTOR"))
    )
    (comp (ref "U$8")
      (value "3.3µH")
      (footprint "eagle-import:IND_VLP8040T-1R0N_TDK")
      (libsource (lib "eagle-import") (part "POWER_INDUCTOR"))
    )
    (comp (ref "U$9")
      (value "3.3µH")
      (footprint "eagle-import:IND_VLP8040T-1R0N_TDK")
      (libsource (lib "eagle-import") (part "POWER_INDUCTOR"))
    )
    (comp (ref "U$10")
      (value "3.3µH")
      (footprint "eagle-import:IND_VLP8040T-1R0N_TDK")
      (libsource (lib "eagle-import") (part "POWER_INDUCTOR"))
    )
    (comp (ref "U$11")
      (value "3.3µH")
      (footprint "eagle-import:IND_VLP8040T-1R0N_TDK")
      (libsource (lib "eagle-import") (part "POWER_INDUCTOR"))
    )
    (comp (ref "U$12")
      (value "3.3µH")
      (footprint "eagle-import:IND_VLP8040T-1R0N_TDK")
      (libsource (lib "eagle-import") (part "POWER_INDUCTOR"))
    )
    (comp (ref "U$13")
      (value "3.3µH")
      (footprint "eagle-import:IND_VLP8040T-1R0N_TDK")
      (libsource (lib "eagle-import") (part "POWER_INDUCTOR"))
    )
    (comp (ref "U$14")
      (value "3.3µH")
      (footprint "eagle-import:IND_VLP8040T-1R0N_TDK")
      (libsource (lib "eagle-import") (part "POWER_INDUCTOR"))
    )
    (comp (ref "U$15")
      (value "3.3µH")
      (footprint "eagle-import:IND_VLP8040T-1R0N_TDK")
      (libsource (lib "eagle-import") (part "POWER_INDUCTOR"))
    )
    (comp (ref "U$16")
      (value "3.3µH")
      (footprint "eagle-import:IND_VLP8040T-1R0N_TDK")
      (libsource (lib "eagle-import") (part "POWER_INDUCTOR"))
    )
    (comp (ref "U$17")
      (value "3.3µH")
      (footprint "eagle-import:IND_VLP8040T-1R0N_TDK")
      (libsource (lib "eagle-import") (part "POWER_INDUCTOR"))
    )
    (comp (ref "U$18")
      (value "3.3µH")
      (footprint "eagle-import:IND_VLP8040T-1R0N_TDK")
      (libsource (lib "eagle-import") (part "POWER_INDUCTOR"))
    )
    (comp (ref "U$19")
      (value "3.3µH")
      (footprint "eagle-import:IND_VLP8040T-1R0N_TDK")
      (libsource (lib "eagle-import") (part "POWER_INDUCTOR"))
    )
    (comp (ref "U$20")
      (value "3.3µH")
      (footprint "eagle-import:IND_VLP8040T-1R0N_TDK")
      (libsource (lib "eagle-import") (part "POWER_INDUCTOR"))
    )
    (comp (ref "U$21")
      (value "3.3µH")
      (footprint "eagle-import:IND_VLP8040T-1R0N_TDK")
      (libsource (lib "eagle-import") (part "POWER_INDUCTOR"))
    )
    (comp (ref "U1")
      (value "TPS562208DDCT")
      (footprint "eagle-import:DDC0006A_N")
      (fields (field (name "COPYRIGHT") "Copyright (C) 2025 Ultra Librarian. All rights reserved."))
      (libsource (lib "eagle-import") (part "TPS562208DDCT"))
    )
    (comp (ref "U2")
      (value "TPS562208DDCT")
      (footprint "eagle-import:DDC0006A_N")
      (fields (field (name "COPYRIGHT") "Copyright (C) 2025 Ultra Librarian. All rights reserved."))
      (libsource (lib "eagle-import") (part "TPS562208DDCT"))
    )
    (comp (ref "U3")
      (value "TPS562208DDCT")
      (footprint "eagle-import:DDC0006A_N")
      (fields (field (name "COPYRIGHT") "Copyright (C) 2025 Ultra Librarian. All rights reserved."))
      (libsource (lib "eagle-import") (part "TPS562208DDCT"))
    )
    (comp (ref "U4")
      (value "TPS562208DDCT")
      (footprint "eagle-import:DDC0006A_N")
      (fields (field (name "COPYRIGHT") "Copyright (C) 2025 Ultra Librarian. All rights reserved."))
      (libsource (lib "eagle-import") (part "TPS562208DDCT"))
    )
    (comp (ref "U5")
      (value "ADM7151ACPZ-04-R7")
      (footprint "eagle-import:CP_8_11_ADI")
      (fields (field (name "COPYRIGHT") "Copyright (C) 2025 Ultra Librarian. All rights reserved."))
      (libsource (lib "eagle-import") (part "ADM7151ACPZ-04-R7"))
    )
    (comp (ref "U6")
      (value "TPS562208DDCT")
      (footprint "eagle-import:DDC0006A_N")
      (fields (field (name "COPYRIGHT") "Copyright (C) 2025 Ultra Librarian. All rights reserved."))
      (libsource (lib "eagle-import") (part "TPS562208DDCT"))
    )
    (comp (ref "U7")
      (value "TPS562208DDCT")
      (footprint "eagle-import:DDC0006A_N")
      (fields (field (name "COPYRIGHT") "Copyright (C) 2025 Ultra Librarian. All rights reserved."))
      (libsource (lib "eagle-import") (part "TPS562208DDCT"))
    )
    (comp (ref "U8")
      (value "TPS562208DDCT")
      (footprint "eagle-import:DDC0006A_N")
      (fields (field (name "COPYRIGHT") "Copyright (C) 2025 Ultra Librarian. All rights reserved."))
      (libsource (lib "eagle-import") (part "TPS562208DDCT"))
    )
    (comp (ref "U9")
      (value "TPS562208DDCT")
      (footprint "eagle-import:DDC0006A_N")
      (fields (field (name "COPYRIGHT") "Copyright (C) 2025 Ultra Librarian. All rights reserved."))
      (libsource (lib "eagle-import") (part "TPS562208DDCT"))
    )
    (comp (ref "U10")
      (value "TPS562208DDCT")
      (footprint "eagle-import:DDC0006A_N")
      (fields (field (name "COPYRIGHT") "Copyright (C) 2025 Ultra Librarian. All rights reserved."))
      (libsource (lib "eagle-import") (part "TPS562208DDCT"))
    )
    (comp (ref "U11")
      (value "TPS562208DDCT")
      (footprint "eagle-import:DDC0006A_N")
      (fields (field (name "COPYRIGHT") "Copyright (C) 2025 Ultra Librarian. All rights reserved."))
      (libsource (lib "eagle-import") (part "TPS562208DDCT"))
    )
    (comp (ref "U12")
      (value "TPS562208DDCT")
      (footprint "eagle-import:DDC0006A_N")
      (fields (field (name "COPYRIGHT") "Copyright (C) 2025 Ultra Librarian. All rights reserved."))
      (libsource (lib "eagle-import") (part "TPS562208DDCT"))
    )
    (comp (ref "U13")
      (value "TPS562208DDCT")
      (footprint "eagle-import:DDC0006A_N")
      (fields (field (name "COPYRIGHT") "Copyright (C) 2025 Ultra Librarian. All rights reserved."))
      (libsource (lib "eagle-import") (part "TPS562208DDCT"))
    )
    (comp (ref "U14")
      (value "TPS562208DDCT")
      (footprint "eagle-import:DDC0006A_N")
      (fields (field (name "COPYRIGHT") "Copyright (C) 2025 Ultra Librarian. All rights reserved."))
      (libsource (lib "eagle-import") (part "TPS562208DDCT"))
    )
    (comp (ref "U15")
      (value "TPS562208DDCT")
      (footprint "eagle-import:DDC0006A_N")
      (fields (field (name "COPYRIGHT") "Copyright (C) 2025 Ultra Librarian. All rights reserved."))
      (libsource (lib "eagle-import") (part "TPS562208DDCT"))
    )
    (comp (ref "U16")
      (value "TPS562208DDCT")
      (footprint "eagle-import:DDC0006A_N")
      (fields (field (name "COPYRIGHT") "Copyright (C) 2025 Ultra Librarian. All rights reserved."))
      (libsource (lib "eagle-import") (part "TPS562208DDCT"))
    )
    (comp (ref "U17")
      (value "TPS562208DDCT")
      (footprint "eagle-import:DDC0006A_N")
      (fields (field (name "COPYRIGHT") "Copyright (C) 2025 Ultra Librarian. All rights reserved."))
      (libsource (lib "eagle-import") (part "TPS562208DDCT"))
    )
    (comp (ref "U18")
      (value "LM2662MX/NOPB")
      (footprint "eagle-import:M08A")
      (fields (field (name "COPYRIGHT") "Copyright (C) 2024 Ultra Librarian. All rights reserved."))
      (libsource (lib "eagle-import") (part "LM2662MX/NOPB"))
    )
    (comp (ref "U19")
      (value "LM2662MX/NOPB")
      (footprint "eagle-import:M08A")
      (fields (field (name "COPYRIGHT") "Copyright (C) 2024 Ultra Librarian. All rights reserved."))
      (libsource (lib "eagle-import") (part "LM2662MX/NOPB"))
    )
    (comp (ref "U20")
      (value "LM2662MX/NOPB")
      (footprint "eagle-import:M08A")
      (fields (field (name "COPYRIGHT") "Copyright (C) 2024 Ultra Librarian. All rights reserved."))
      (libsource (lib "eagle-import") (part "LM2662MX/NOPB"))
    )
    (comp (ref "U21")
      (value "LM2662MX/NOPB")
      (footprint "eagle-import:M08A")
      (fields (field (name "COPYRIGHT") "Copyright (C) 2024 Ultra Librarian. All rights reserved."))
      (libsource (lib "eagle-import") (part "LM2662MX/NOPB"))
    )
    (comp (ref "U22")
      (value "LM2662MX/NOPB")
      (footprint "eagle-import:M08A")
      (fields (field (name "COPYRIGHT") "Copyright (C) 2024 Ultra Librarian. All rights reserved."))
      (libsource (lib "eagle-import") (part "LM2662MX/NOPB"))
    )
    (comp (ref "U23")
      (value "ADM7151ACPZ-04-R7")
      (footprint "eagle-import:CP_8_11_ADI")
      (fields (field (name "COPYRIGHT") "Copyright (C) 2025 Ultra Librarian. All rights reserved."))
      (libsource (lib "eagle-import") (part "ADM7151ACPZ-04-R7"))
    )
    (comp (ref "U24")
      (value "TPS562208DDCT")
      (footprint "eagle-import:DDC0006A_N")
      (fields (field (name "COPYRIGHT") "Copyright (C) 2025 Ultra Librarian. All rights reserved."))
      (libsource (lib "eagle-import") (part "TPS562208DDCT"))
    )
    (comp (ref "U25")
      (value "ADM7151ACPZ-04-R7")
      (footprint "eagle-import:CP_8_11_ADI")
      (fields (field (name "COPYRIGHT") "Copyright (C) 2025 Ultra Librarian. All rights reserved."))
      (libsource (lib "eagle-import") (part "ADM7151ACPZ-04-R7"))
    )
    (comp (ref "U26")
      (value "TPS562208DDCT")
      (footprint "eagle-import:DDC0006A_N")
      (fields (field (name "COPYRIGHT") "Copyright (C) 2025 Ultra Librarian. All rights reserved."))
      (libsource (lib "eagle-import") (part "TPS562208DDCT"))
    )
    (comp (ref "U27")
      (value "ADM7151ACPZ-04-R7")
      (footprint "eagle-import:CP_8_11_ADI")
      (fields (field (name "COPYRIGHT") "Copyright (C) 2025 Ultra Librarian. All rights reserved."))
      (libsource (lib "eagle-import") (part "ADM7151ACPZ-04-R7"))
    )
    (comp (ref "U28")
      (value "TPS562208DDCT")
      (footprint "eagle-import:DDC0006A_N")
      (fields (field (name "COPYRIGHT") "Copyright (C) 2025 Ultra Librarian. All rights reserved."))
      (libsource (lib "eagle-import") (part "TPS562208DDCT"))
    )
    (comp (ref "U29")
      (value "ADM7151ACPZ-04-R7")
      (footprint "eagle-import:CP_8_11_ADI")
      (fields (field (name "COPYRIGHT") "Copyright (C) 2025 Ultra Librarian. All rights reserved."))
      (libsource (lib "eagle-import") (part "ADM7151ACPZ-04-R7"))
    )
    (comp (ref "U30")
      (value "ADM7151ACPZ-04-R7")
      (footprint "eagle-import:CP_8_11_ADI")
      (fields (field (name "COPYRIGHT") "Copyright (C) 2025 Ultra Librarian. All rights reserved."))
      (libsource (lib "eagle-import") (part "ADM7151ACPZ-04-R7"))
    )
    (comp (ref "U31")
      (value "TPS562208DDCT")
      (footprint "eagle-import:DDC0006A_N")
      (fields (field (name "COPYRIGHT") "Copyright (C) 2025 Ultra Librarian. All rights reserved."))
      (libsource (lib "eagle-import") (part "TPS562208DDCT"))
    )
    (comp (ref "U32")
      (value "TPS7A8300RGRR")
      (footprint "eagle-import:RGR20_2P05X2P05_TEX")
      (fields (field (name "COPYRIGHT") "Copyright (C) 2025 Ultra Librarian. All rights reserved."))
      (libsource (lib "eagle-import") (part "TPS7A8300RGRR"))
    )
    (comp (ref "U33")
      (value "TPS562208DDCT")
      (footprint "eagle-import:DDC0006A_N")
      (fields (field (name "COPYRIGHT") "Copyright (C) 2025 Ultra Librarian. All rights reserved."))
      (libsource (lib "eagle-import") (part "TPS562208DDCT"))
    )
    (comp (ref "U34")
      (value "TPS7A8300RGRR")
      (footprint "eagle-import:RGR20_2P05X2P05_TEX")
      (fields (field (name "COPYRIGHT") "Copyright (C) 2025 Ultra Librarian. All rights reserved."))
      (libsource (lib "eagle-import") (part "TPS7A8300RGRR"))
    )
    (comp (ref "X1")
      (value "AK300/2")
      (footprint "eagle-import:AK300_2")
      (libsource (lib "eagle-import") (part "AK300/2"))
    )
    (comp (ref "X2")
      (value "22-23-2021")
      (footprint "eagle-import:22-23-2021")
      (fields (field (name "MF") "MOLEX"))
      (libsource (lib "eagle-import") (part "22-23-2021"))
    )
    (comp (ref "X3")
      (value "22-23-2021")
      (footprint "eagle-import:22-23-2021")
      (fields (field (name "MF") "MOLEX"))
      (libsource (lib "eagle-import") (part "22-23-2021"))
    )
    (comp (ref "X4")
      (value "22-23-2021")
      (footprint "eagle-import:22-23-2021")
      (fields (field (name "MF") "MOLEX"))
      (libsource (lib "eagle-import") (part "22-23-2021"))
    )
    (comp (ref "X5")
      (value "22-23-2021")
      (footprint "eagle-import:22-23-2021")
      (fields (field (name "MF") "MOLEX"))
      (libsource (lib "eagle-import") (part "22-23-2021"))
    )
    (comp (ref "X6")
      (value "22-23-2021")
      (footprint "eagle-import:22-23-2021")
      (fields (field (name "MF") "MOLEX"))
      (libsource (lib "eagle-import") (part "22-23-2021"))
    )
    (comp (ref "X7")
      (value "22-23-2021")
      (footprint "eagle-import:22-23-2021")
      (fields (field (name "MF") "MOLEX"))
      (libsource (lib "eagle-import") (part "22-23-2021"))
    )
    (comp (ref "X8")
      (value "22-23-2021")
      (footprint "eagle-import:22-23-2021")
      (fields (field (name "MF") "MOLEX"))
      (libsource (lib "eagle-import") (part "22-23-2021"))
    )
    (comp (ref "X9")
      (value "22-23-2021")
      (footprint "eagle-import:22-23-2021")
      (fields (field (name "MF") "MOLEX"))
      (libsource (lib "eagle-import") (part "22-23-2021"))
    )
    (comp (ref "X10")
      (value "22-23-2021")
      (footprint "eagle-import:22-23-2021")
      (fields (field (name "MF") "MOLEX"))
      (libsource (lib "eagle-import") (part "22-23-2021"))
    )
    (comp (ref "X11")
      (value "22-23-2021")
      (footprint "eagle-import:22-23-2021")
      (fields (field (name "MF") "MOLEX"))
      (libsource (lib "eagle-import") (part "22-23-2021"))
    )
    (comp (ref "X12")
      (value "22-23-2021")
      (footprint "eagle-import:22-23-2021")
      (fields (field (name "MF") "MOLEX"))
      (libsource (lib "eagle-import") (part "22-23-2021"))
    )
    (comp (ref "X13")
      (value "22-23-2021")
      (footprint "eagle-import:22-23-2021")
      (fields (field (name "MF") "MOLEX"))
      (libsource (lib "eagle-import") (part "22-23-2021"))
    )
    (comp (ref "X14")
      (value "22-23-2021")
      (footprint "eagle-import:22-23-2021")
      (fields (field (name "MF") "MOLEX"))
      (libsource (lib "eagle-import") (part "22-23-2021"))
    )
    (comp (ref "X15")
      (value "22-23-2021")
      (footprint "eagle-import:22-23-2021")
      (fields (field (name "MF") "MOLEX"))
      (libsource (lib "eagle-import") (part "22-23-2021"))
    )
    (comp (ref "X16")
      (value "22-23-2021")
      (footprint "eagle-import:22-23-2021")
      (fields (field (name "MF") "MOLEX"))
      (libsource (lib "eagle-import") (part "22-23-2021"))
    )
    (comp (ref "X17")
      (value "22-23-2021")
      (footprint "eagle-import:22-23-2021")
      (fields (field (name "MF") "MOLEX"))
      (libsource (lib "eagle-import") (part "22-23-2021"))
    )
    (comp (ref "X18")
      (value "22-23-2021")
      (footprint "eagle-import:22-23-2021")
      (fields (field (name "MF") "MOLEX"))
      (libsource (lib "eagle-import") (part "22-23-2021"))
    )
    (comp (ref "X19")
      (value "22-23-2021")
      (footprint "eagle-import:22-23-2021")
      (fields (field (name "MF") "MOLEX"))
      (libsource (lib "eagle-import") (part "22-23-2021"))
    )
    (comp (ref "X20")
      (value "22-23-2021")
      (footprint "eagle-import:22-23-2021")
      (fields (field (name "MF") "MOLEX"))
      (libsource (lib "eagle-import") (part "22-23-2021"))
    )
    (comp (ref "X21")
      (value "22-23-2021")
      (footprint "eagle-import:22-23-2021")
      (fields (field (name "MF") "MOLEX"))
      (libsource (lib "eagle-import") (part "22-23-2021"))
    )
    (comp (ref "X22")
      (value "22-23-2021")
      (footprint "eagle-import:22-23-2021")
      (fields (field (name "MF") "MOLEX"))
      (libsource (lib "eagle-import") (part "22-23-2021"))
    )
    (comp (ref "X23")
      (value "22-23-2021")
      (footprint "eagle-import:22-23-2021")
      (fields (field (name "MF") "MOLEX"))
      (libsource (lib "eagle-import") (part "22-23-2021"))
    )
    (comp (ref "X24")
      (value "22-23-2021")
      (footprint "eagle-import:22-23-2021")
      (fields (field (name "MF") "MOLEX"))
      (libsource (lib "eagle-import") (part "22-23-2021"))
    )
    (comp (ref "X25")
      (value "22-23-2021")
      (footprint "eagle-import:22-23-2021")
      (fields (field (name "MF") "MOLEX"))
      (libsource (lib "eagle-import") (part "22-23-2021"))
    )
    (comp (ref "X26")
      (value "22-23-2021")
      (footprint "eagle-import:22-23-2021")
      (fields (field (name "MF") "MOLEX"))
      (libsource (lib "eagle-import") (part "22-23-2021"))
    )
    (comp (ref "X27")
      (value "22-23-2021")
      (footprint "eagle-import:22-23-2021")
      (fields (field (name "MF") "MOLEX"))
      (libsource (lib "eagle-import") (part "22-23-2021"))
    )
    (comp (ref "X28")
      (value "22-23-2021")
      (footprint "eagle-import:22-23-2021")
      (fields (field (name "MF") "MOLEX"))
      (libsource (lib "eagle-import") (part "22-23-2021"))
    )
    (comp (ref "X29")
      (value "22-23-2021")
      (footprint "eagle-import:22-23-2021")
      (fields (field (name "MF") "MOLEX"))
      (libsource (lib "eagle-import") (part "22-23-2021"))
    )
    (comp (ref "X30")
      (value "22-23-2021")
      (footprint "eagle-import:22-23-2021")
      (fields (field (name "MF") "MOLEX"))
      (libsource (lib "eagle-import") (part "22-23-2021"))
    )
    (comp (ref "X31")
      (value "22-23-2021")
      (footprint "eagle-import:22-23-2021")
      (fields (field (name "MF") "MOLEX"))
      (libsource (lib "eagle-import") (part "22-23-2021"))
    )
    (comp (ref "X32")
      (value "22-23-2021")
      (footprint "eagle-import:22-23-2021")
      (fields (field (name "MF") "MOLEX"))
      (libsource (lib "eagle-import") (part "22-23-2021"))
    )
    (comp (ref "X33")
      (value "22-23-2021")
      (footprint "eagle-import:22-23-2021")
      (fields (field (name "MF") "MOLEX"))
      (libsource (lib "eagle-import") (part "22-23-2021"))
    )
    (comp (ref "X34")
      (value "22-23-2021")
      (footprint "eagle-import:22-23-2021")
      (fields (field (name "MF") "MOLEX"))
      (libsource (lib "eagle-import") (part "22-23-2021"))
    )
    (comp (ref "X35")
      (value "22-23-2021")
      (footprint "eagle-import:22-23-2021")
      (fields (field (name "MF") "MOLEX"))
      (libsource (lib "eagle-import") (part "22-23-2021"))
    )
  )
  (nets
    (net (code "1") (name "/+1V0_FPGA") (class "Default")
      (node (ref "C2") (pin "1") (pinfunction "1_1") (pintype "passive"))
      (node (ref "C3") (pin "1") (pinfunction "1_1") (pintype "passive"))
      (node (ref "R1") (pin "2") (pinfunction "2_2") (pintype "passive"))
      (node (ref "U$1") (pin "1") (pinfunction "1_1") (pintype "passive"))
      (node (ref "X4") (pin "1") (pinfunction "S_1") (pintype "passive"))
    )
    (net (code "2") (name "/+1V8_CLOCK") (class "Default")
      (node (ref "C115") (pin "2") (pinfunction "2_2") (pintype "passive"))
      (node (ref "U25") (pin "2") (pinfunction "VOUT_2") (pintype "output"))
      (node (ref "X10") (pin "1") (pinfunction "S_1") (pintype "passive"))
    )
    (net (code "3") (name "/+1V8_FPGA") (class "Default")
      (node (ref "C11") (pin "1") (pinfunction "1_1") (pintype "passive"))
      (node (ref "C7") (pin "1") (pinfunction "1_1") (pintype "passive"))
      (node (ref "C8") (pin "1") (pinfunction "1_1") (pintype "passive"))
      (node (ref "R3") (pin "2") (pinfunction "2_2") (pintype "passive"))
      (node (ref "U$2") (pin "1") (pinfunction "1_1") (pintype "passive"))
      (node (ref "X5") (pin "1") (pinfunction "S_1") (pintype "passive"))
    )
    (net (code "4") (name "/+3V3") (class "Default")
      (node (ref "C13") (pin "1") (pinfunction "1_1") (pintype "passive"))
      (node (ref "C14") (pin "1") (pinfunction "1_1") (pintype "passive"))
      (node (ref "C17") (pin "1") (pinfunction "1_1") (pintype "passive"))
      (node (ref "R5") (pin "2") (pinfunction "2_2") (pintype "passive"))
      (node (ref "U$3") (pin "1") (pinfunction "1_1") (pintype "passive"))
      (node (ref "X16") (pin "1") (pinfunction "S_1") (pintype "passive"))
    )
    (net (code "5") (name "/+3V3_ADAR_12") (class "Default")
      (node (ref "C31") (pin "1") (pinfunction "1_1") (pintype "passive"))
      (node (ref "C32") (pin "1") (pinfunction "1_1") (pintype "passive"))
      (node (ref "C35") (pin "1") (pinfunction "1_1") (pintype "passive"))
      (node (ref "R11") (pin "2") (pinfunction "2_2") (pintype "passive"))
      (node (ref "U$6") (pin "1") (pinfunction "1_1") (pintype "passive"))
      (node (ref "X14") (pin "1") (pinfunction "S_1") (pintype "passive"))
    )
    (net (code "6") (name "/+3V3_ADAR_34") (class "Default")
      (node (ref "C37") (pin "1") (pinfunction "1_1") (pintype "passive"))
      (node (ref "C38") (pin "1") (pinfunction "1_1") (pintype "passive"))
      (node (ref "C41") (pin "1") (pinfunction "1_1") (pintype "passive"))
      (node (ref "R13") (pin "2") (pinfunction "2_2") (pintype "passive"))
      (node (ref "U$7") (pin "1") (pinfunction "1_1") (pintype "passive"))
      (node (ref "X15") (pin "1") (pinfunction "S_1") (pintype "passive"))
    )
    (net (code "7") (name "/+3V3_ADTR") (class "Default")
      (node (ref "C149") (pin "1") (pinfunction "1_1") (pintype "passive"))
      (node (ref "R53") (pin "2") (pinfunction "2_2") (pintype "passive"))
      (node (ref "U32") (pin "1") (pinfunction "OUT_2_1") (pintype "output"))
      (node (ref "U32") (pin "19") (pinfunction "OUT_3_19") (pintype "output"))
      (node (ref "U32") (pin "20") (pinfunction "OUT_20") (pintype "output"))
      (node (ref "X34") (pin "1") (pinfunction "S_1") (pintype "passive"))
    )
    (net (code "8") (name "/+3V3_AN") (class "Default")
      (node (ref "C25") (pin "2") (pinfunction "2_2") (pintype "passive"))
      (node (ref "U5") (pin "2") (pinfunction "VOUT_2") (pintype "output"))
      (node (ref "X12") (pin "1") (pinfunction "S_1") (pintype "passive"))
    )
    (net (code "9") (name "/+3V3_CLOCK") (class "Default")
      (node (ref "C53") (pin "2") (pinfunction "2_2") (pintype "passive"))
      (node (ref "U23") (pin "2") (pinfunction "VOUT_2") (pintype "output"))
      (node (ref "X11") (pin "1") (pinfunction "S_1") (pintype "passive"))
    )
    (net (code "10") (name "/+3V3_FPGA") (class "Default")
      (node (ref "C19") (pin "1") (pinfunction "1_1") (pintype "passive"))
      (node (ref "C20") (pin "1") (pinfunction "1_1") (pintype "passive"))
      (node (ref "C23") (pin "1") (pinfunction "1_1") (pintype "passive"))
      (node (ref "R7") (pin "2") (pinfunction "2_2") (pintype "passive"))
      (node (ref "U$4") (pin "1") (pinfunction "1_1") (pintype "passive"))
      (node (ref "X27") (pin "1") (pinfunction "S_1") (pintype "passive"))
    )
    (net (code "11") (name "/+3V3_LO_1") (class "Default")
      (node (ref "C125") (pin "2") (pinfunction "2_2") (pintype "passive"))
      (node (ref "U27") (pin "2") (pinfunction "VOUT_2") (pintype "output"))
      (node (ref "X8") (pin "1") (pinfunction "S_1") (pintype "passive"))
    )
    (net (code "12") (name "/+3V3_LO_2") (class "Default")
      (node (ref "C135") (pin "2") (pinfunction "2_2") (pintype "passive"))
      (node (ref "U29") (pin "2") (pinfunction "VOUT_2") (pintype "output"))
      (node (ref "X7") (pin "1") (pinfunction "S_1") (pintype "passive"))
    )
    (net (code "13") (name "/+3V3_SW") (class "Default")
      (node (ref "C55") (pin "1") (pinfunction "1_1") (pintype "passive"))
      (node (ref "C56") (pin "1") (pinfunction "1_1") (pintype "passive"))
      (node (ref "C59") (pin "1") (pinfunction "1_1") (pintype "passive"))
      (node (ref "R19") (pin "2") (pinfunction "2_2") (pintype "passive"))
      (node (ref "U$10") (pin "1") (pinfunction "1_1") (pintype "passive"))
      (node (ref "U18") (pin "8") (pinfunction "V+_8") (pintype "input"))
      (node (ref "X29") (pin "1") (pinfunction "S_1") (pintype "passive"))
    )
    (net (code "14") (name "/+3V3_VDD_SW") (class "Default")
      (node (ref "C43") (pin "1") (pinfunction "1_1") (pintype "passive"))
      (node (ref "C44") (pin "1") (pinfunction "1_1") (pintype "passive"))
      (node (ref "C47") (pin "1") (pinfunction "1_1") (pintype "passive"))
      (node (ref "R15") (pin "2") (pinfunction "2_2") (pintype "passive"))
      (node (ref "U$8") (pin "1") (pinfunction "1_1") (pintype "passive"))
      (node (ref "X30") (pin "1") (pinfunction "S_1") (pintype "passive"))
    )
    (net (code "15") (name "/+3V3_XO") (class "Default")
      (node (ref "C159") (pin "1") (pinfunction "1_1") (pintype "passive"))
      (node (ref "R57") (pin "2") (pinfunction "2_2") (pintype "passive"))
      (node (ref "U34") (pin "1") (pinfunction "OUT_2_1") (pintype "output"))
      (node (ref "U34") (pin "19") (pinfunction "OUT_3_19") (pintype "output"))
      (node (ref "U34") (pin "20") (pinfunction "OUT_20") (pintype "output"))
      (node (ref "X35") (pin "1") (pinfunction "S_1") (pintype "passive"))
    )
    (net (code "16") (name "/+3V4") (class "Default")
      (node (ref "C61") (pin "1") (pinfunction "1_1") (pintype "passive"))
      (node (ref "C62") (pin "1") (pinfunction "1_1") (pintype "passive"))
      (node (ref "C65") (pin "1") (pinfunction "1_1") (pintype "passive"))
      (node (ref "R21") (pin "2") (pinfunction "2_2") (pintype "passive"))
      (node (ref "U$11") (pin "1") (pinfunction "1_1") (pintype "passive"))
      (node (ref "U19") (pin "8") (pinfunction "V+_8") (pintype "input"))
      (node (ref "X23") (pin "1") (pinfunction "S_1") (pintype "passive"))
    )
    (net (code "17") (name "/+5V0_0") (class "Default")
      (node (ref "C28") (pin "2") (pinfunction "2_2") (pintype "passive"))
      (node (ref "C67") (pin "1") (pinfunction "1_1") (pintype "passive"))
      (node (ref "C68") (pin "1") (pinfunction "1_1") (pintype "passive"))
      (node (ref "R23") (pin "2") (pinfunction "2_2") (pintype "passive"))
      (node (ref "U$12") (pin "1") (pinfunction "1_1") (pintype "passive"))
      (node (ref "U5") (pin "7") (pinfunction "EN_7") (pintype "input"))
      (node (ref "U5") (pin "8") (pinfunction "VIN_8") (pintype "input"))
      (node (ref "X22") (pin "1") (pinfunction "S_1") (pintype "passive"))
    )
    (net (code "18") (name "/+5V0_1") (class "Default")
      (node (ref "C108") (pin "2") (pinfunction "2_2") (pintype "passive"))
      (node (ref "C48") (pin "1") (pinfunction "1_1") (pintype "passive"))
      (node (ref "C49") (pin "1") (pinfunction "1_1") (pintype "passive"))
      (node (ref "R17") (pin "2") (pinfunction "2_2") (pintype "passive"))
      (node (ref "U$5") (pin "1") (pinfunction "1_1") (pintype "passive"))
      (node (ref "U23") (pin "8") (pinfunction "VIN_8") (pintype "input"))
      (node (ref "X2") (pin "1") (pinfunction "S_1") (pintype "passive"))
    )
    (net (code "19") (name "/+5V0_2") (class "Default")
      (node (ref "C110") (pin "1") (pinfunction "1_1") (pintype "passive"))
      (node (ref "C111") (pin "1") (pinfunction "1_1") (pintype "passive"))
      (node (ref "C118") (pin "2") (pinfunction "2_2") (pintype "passive"))
      (node (ref "R37") (pin "2") (pinfunction "2_2") (pintype "passive"))
      (node (ref "U$9") (pin "1") (pinfunction "1_1") (pintype "passive"))
      (node (ref "U25") (pin "8") (pinfunction "VIN_8") (pintype "input"))
      (node (ref "X9") (pin "1") (pinfunction "S_1") (pintype "passive"))
    )
    (net (code "20") (name "/+5V0_3") (class "Default")
      (node (ref "C120") (pin "1") (pinfunction "1_1") (pintype "passive"))
      (node (ref "C121") (pin "1") (pinfunction "1_1") (pintype "passive"))
      (node (ref "C128") (pin "2") (pinfunction "2_2") (pintype "passive"))
      (node (ref "R41") (pin "2") (pinfunction "2_2") (pintype "passive"))
      (node (ref "U$18") (pin "1") (pinfunction "1_1") (pintype "passive"))
      (node (ref "U27") (pin "7") (pinfunction "EN_7") (pintype "input"))
      (node (ref "U27") (pin "8") (pinfunction "VIN_8") (pintype "input"))
      (node (ref "X17") (pin "1") (pinfunction "S_1") (pintype "passive"))
    )
    (net (code "21") (name "/+5V0_4") (class "Default")
      (node (ref "C130") (pin "1") (pinfunction "1_1") (pintype "passive"))
      (node (ref "C131") (pin "1") (pinfunction "1_1") (pintype "passive"))
      (node (ref "C138") (pin "2") (pinfunction "2_2") (pintype "passive"))
      (node (ref "R45") (pin "2") (pinfunction "2_2") (pintype "passive"))
      (node (ref "U$19") (pin "1") (pinfunction "1_1") (pintype "passive"))
      (node (ref "U29") (pin "7") (pinfunction "EN_7") (pintype "input"))
      (node (ref "U29") (pin "8") (pinfunction "VIN_8") (pintype "input"))
      (node (ref "X25") (pin "1") (pinfunction "S_1") (pintype "passive"))
    )
    (net (code "22") (name "/+5V0_5") (class "Default")
      (node (ref "C155") (pin "1") (pinfunction "1_1") (pintype "passive"))
      (node (ref "C156") (pin "1") (pinfunction "1_1") (pintype "passive"))
      (node (ref "C163") (pin "1") (pinfunction "1_1") (pintype "passive"))
      (node (ref "R55") (pin "2") (pinfunction "2_2") (pintype "passive"))
      (node (ref "U$21") (pin "1") (pinfunction "1_1") (pintype "passive"))
      (node (ref "U34") (pin "14") (pinfunction "EN_14") (pintype "input"))
      (node (ref "U34") (pin "15") (pinfunction "IN_2_15") (pintype "input"))
      (node (ref "U34") (pin "16") (pinfunction "IN_3_16") (pintype "input"))
      (node (ref "U34") (pin "17") (pinfunction "IN_17") (pintype "input"))
      (node (ref "X28") (pin "1") (pinfunction "S_1") (pintype "passive"))
    )
    (net (code "23") (name "/+5V0_ADAR") (class "Default")
      (node (ref "C72") (pin "1") (pinfunction "1_1") (pintype "passive"))
      (node (ref "C73") (pin "1") (pinfunction "1_1") (pintype "passive"))
      (node (ref "R25") (pin "2") (pinfunction "2_2") (pintype "passive"))
      (node (ref "U$13") (pin "1") (pinfunction "1_1") (pintype "passive"))
      (node (ref "U20") (pin "8") (pinfunction "V+_8") (pintype "input"))
      (node (ref "U21") (pin "8") (pinfunction "V+_8") (pintype "input"))
      (node (ref "X13") (pin "1") (pinfunction "S_1") (pintype "passive"))
    )
    (net (code "24") (name "/+5V0_ADTR") (class "Default")
      (node (ref "C145") (pin "1") (pinfunction "1_1") (pintype "passive"))
      (node (ref "C146") (pin "1") (pinfunction "1_1") (pintype "passive"))
      (node (ref "C153") (pin "1") (pinfunction "1_1") (pintype "passive"))
      (node (ref "R51") (pin "2") (pinfunction "2_2") (pintype "passive"))
      (node (ref "U$20") (pin "1") (pinfunction "1_1") (pintype "passive"))
      (node (ref "U32") (pin "15") (pinfunction "IN_2_15") (pintype "input"))
      (node (ref "U32") (pin "16") (pinfunction "IN_3_16") (pintype "input"))
      (node (ref "U32") (pin "17") (pinfunction "IN_17") (pintype "input"))
      (node (ref "X26") (pin "1") (pinfunction "S_1") (pintype "passive"))
    )
    (net (code "25") (name "/+5V0_LO") (class "Default")
      (node (ref "C140") (pin "2") (pinfunction "2_2") (pintype "passive"))
      (node (ref "U30") (pin "2") (pinfunction "VOUT_2") (pintype "output"))
      (node (ref "X6") (pin "1") (pinfunction "S_1") (pintype "passive"))
    )
    (net (code "26") (name "/+5V0_PA_1") (class "Default")
      (node (ref "C78") (pin "1") (pinfunction "1_1") (pintype "passive"))
      (node (ref "C79") (pin "1") (pinfunction "1_1") (pintype "passive"))
      (node (ref "R27") (pin "2") (pinfunction "2_2") (pintype "passive"))
      (node (ref "U$14") (pin "1") (pinfunction "1_1") (pintype "passive"))
      (node (ref "X31") (pin "1") (pinfunction "S_1") (pintype "passive"))
    )
    (net (code "27") (name "/+5V0_PA_2") (class "Default")
      (node (ref "C84") (pin "1") (pinfunction "1_1") (pintype "passive"))
      (node (ref "C85") (pin "1") (pinfunction "1_1") (pintype "passive"))
      (node (ref "R29") (pin "2") (pinfunction "2_2") (pintype "passive"))
      (node (ref "U$15") (pin "1") (pinfunction "1_1") (pintype "passive"))
      (node (ref "X32") (pin "1") (pinfunction "S_1") (pintype "passive"))
    )
    (net (code "28") (name "/+5V0_PA_3") (class "Default")
      (node (ref "C90") (pin "1") (pinfunction "1_1") (pintype "passive"))
      (node (ref "C91") (pin "1") (pinfunction "1_1") (pintype "passive"))
      (node (ref "R31") (pin "2") (pinfunction "2_2") (pintype "passive"))
      (node (ref "U$16") (pin "1") (pinfunction "1_1") (pintype "passive"))
      (node (ref "X33") (pin "1") (pinfunction "S_1") (pintype "passive"))
    )
    (net (code "29") (name "/+5V5_PA") (class "Default")
      (node (ref "C82") (pin "1") (pinfunction "1_1") (pintype "passive"))
      (node (ref "C88") (pin "1") (pinfunction "1_1") (pintype "passive"))
      (node (ref "R33") (pin "2") (pinfunction "2_2") (pintype "passive"))
      (node (ref "U$17") (pin "1") (pinfunction "1_1") (pintype "passive"))
      (node (ref "U22") (pin "8") (pinfunction "V+_8") (pintype "input"))
      (node (ref "X3") (pin "1") (pinfunction "S_1") (pintype "passive"))
    )
    (net (code "30") (name "/-3V3_SW") (class "Default")
      (node (ref "C97") (pin "2") (pinfunction "-_2") (pintype "bidirectional"))
      (node (ref "U18") (pin "5") (pinfunction "OUT_5") (pintype "output"))
      (node (ref "X18") (pin "1") (pinfunction "S_1") (pintype "passive"))
    )
    (net (code "31") (name "/-3V4") (class "Default")
      (node (ref "C99") (pin "2") (pinfunction "-_2") (pintype "bidirectional"))
      (node (ref "U19") (pin "5") (pinfunction "OUT_5") (pintype "output"))
      (node (ref "X24") (pin "1") (pinfunction "S_1") (pintype "passive"))
    )
    (net (code "32") (name "/-5V0_ADAR12") (class "Default")
      (node (ref "C101") (pin "2") (pinfunction "-_2") (pintype "bidirectional"))
      (node (ref "U20") (pin "5") (pinfunction "OUT_5") (pintype "output"))
      (node (ref "X21") (pin "1") (pinfunction "S_1") (pintype "passive"))
    )
    (net (code "33") (name "/-5V0_ADAR34") (class "Default")
      (node (ref "C103") (pin "2") (pinfunction "-_2") (pintype "bidirectional"))
      (node (ref "U21") (pin "5") (pinfunction "OUT_5") (pintype "output"))
      (node (ref "X20") (pin "1") (pinfunction "S_1") (pintype "passive"))
    )
    (net (code "34") (name "/-5V5_PA") (class "Default")
      (node (ref "C105") (pin "2") (pinfunction "-_2") (pintype "bidirectional"))
      (node (ref "U22") (pin "5") (pinfunction "OUT_5") (pintype "output"))
      (node (ref "X19") (pin "1") (pinfunction "S_1") (pintype "passive"))
    )
    (net (code "35") (name "/EN_+1V0_FPGA") (class "Default")
      (node (ref "SV1") (pin "1") (pinfunction "1_1") (pintype "passive"))
      (node (ref "U1") (pin "5") (pinfunction "EN_5") (pintype "input"))
    )
    (net (code "36") (name "/EN_+1V8_CLOCK") (class "Default")
      (node (ref "SV1") (pin "8") (pinfunction "8_8") (pintype "passive"))
      (node (ref "U25") (pin "7") (pinfunction "EN_7") (pintype "input"))
    )
    (net (code "37") (name "/EN_+1V8_FPGA") (class "Default")
      (node (ref "SV1") (pin "3") (pinfunction "3_3") (pintype "passive"))
      (node (ref "U2") (pin "5") (pinfunction "EN_5") (pintype "input"))
    )
    (net (code "38") (name "/EN_+3V3_ADAR12") (class "Default")
      (node (ref "SV1") (pin "9") (pinfunction "9_9") (pintype "passive"))
      (node (ref "U6") (pin "5") (pinfunction "EN_5") (pintype "input"))
    )
    (net (code "39") (name "/EN_+3V3_ADAR34") (class "Default")
      (node (ref "SV1") (pin "11") (pinfunction "11_11") (pintype "passive"))
      (node (ref "U7") (pin "5") (pinfunction "EN_5") (pintype "input"))
    )
    (net (code "40") (name "/EN_+3V3_ADTR") (class "Default")
      (node (ref "SV1") (pin "13") (pinfunction "13_13") (pintype "passive"))
      (node (ref "U32") (pin "14") (pinfunction "EN_14") (pintype "input"))
    )
    (net (code "41") (name "/EN_+3V3_CLOCK") (class "Default")
      (node (ref "SV1") (pin "10") (pinfunction "10_10") (pintype "passive"))
      (node (ref "U23") (pin "7") (pinfunction "EN_7") (pintype "input"))
    )
    (net (code "42") (name "/EN_+3V3_FPGA") (class "Default")
      (node (ref "SV1") (pin "5") (pinfunction "5_5") (pintype "passive"))
      (node (ref "U4") (pin "5") (pinfunction "EN_5") (pintype "input"))
    )
    (net (code "43") (name "/EN_+3V3_SW") (class "Default")
      (node (ref "SV1") (pin "15") (pinfunction "15_15") (pintype "passive"))
      (node (ref "U10") (pin "5") (pinfunction "EN_5") (pintype "input"))
    )
    (net (code "44") (name "/EN_+3V3_VDD_SW") (class "Default")
      (node (ref "SV1") (pin "17") (pinfunction "17_17") (pintype "passive"))
      (node (ref "U8") (pin "5") (pinfunction "EN_5") (pintype "input"))
    )
    (net (code "45") (name "/EN_+5V0_ADAR") (class "Default")
      (node (ref "SV1") (pin "7") (pinfunction "7_7") (pintype "passive"))
      (node (ref "U13") (pin "5") (pinfunction "EN_5") (pintype "input"))
    )
    (net (code "46") (name "/EN_+5V0_PA1") (class "Default")
      (node (ref "SV1") (pin "19") (pinfunction "19_19") (pintype "passive"))
      (node (ref "U14") (pin "5") (pinfunction "EN_5") (pintype "input"))
    )
    (net (code "47") (name "/EN_+5V0_PA2") (class "Default")
      (node (ref "SV1") (pin "2") (pinfunction "2_2") (pintype "passive"))
      (node (ref "U15") (pin "5") (pinfunction "EN_5") (pintype "input"))
    )
    (net (code "48") (name "/EN_+5V0_PA3") (class "Default")
      (node (ref "SV1") (pin "4") (pinfunction "4_4") (pintype "passive"))
      (node (ref "U16") (pin "5") (pinfunction "EN_5") (pintype "input"))
    )
    (net (code "49") (name "/EN_+5V5_PA") (class "Default")
      (node (ref "SV1") (pin "6") (pinfunction "6_6") (pintype "passive"))
      (node (ref "U17") (pin "5") (pinfunction "EN_5") (pintype "input"))
    )
    (net (code "50") (name "/VIN") (class "Default")
      (node (ref "C10") (pin "1") (pinfunction "1_1") (pintype "passive"))
      (node (ref "C112") (pin "1") (pinfunction "1_1") (pintype "passive"))
      (node (ref "C113") (pin "1") (pinfunction "1_1") (pintype "passive"))
      (node (ref "C122") (pin "1") (pinfunction "1_1") (pintype "passive"))
      (node (ref "C123") (pin "1") (pinfunction "1_1") (pintype "passive"))
      (node (ref "C132") (pin "1") (pinfunction "1_1") (pintype "passive"))
      (node (ref "C133") (pin "1") (pinfunction "1_1") (pintype "passive"))
      (node (ref "C143") (pin "2") (pinfunction "2_2") (pintype "passive"))
      (node (ref "C147") (pin "1") (pinfunction "1_1") (pintype "passive"))
      (node (ref "C148") (pin "1") (pinfunction "1_1") (pintype "passive"))
      (node (ref "C15") (pin "1") (pinfunction "1_1") (pintype "passive"))
      (node (ref "C157") (pin "1") (pinfunction "1_1") (pintype "passive"))
      (node (ref "C158") (pin "1") (pinfunction "1_1") (pintype "passive"))
      (node (ref "C16") (pin "1") (pinfunction "1_1") (pintype "passive"))
      (node (ref "C21") (pin "1") (pinfunction "1_1") (pintype "passive"))
      (node (ref "C22") (pin "1") (pinfunction "1_1") (pintype "passive"))
      (node (ref "C33") (pin "1") (pinfunction "1_1") (pintype "passive"))
      (node (ref "C34") (pin "1") (pinfunction "1_1") (pintype "passive"))
      (node (ref "C39") (pin "1") (pinfunction "1_1") (pintype "passive"))
      (node (ref "C4") (pin "1") (pinfunction "1_1") (pintype "passive"))
      (node (ref "C40") (pin "1") (pinfunction "1_1") (pintype "passive"))
      (node (ref "C45") (pin "1") (pinfunction "1_1") (pintype "passive"))
      (node (ref "C46") (pin "1") (pinfunction "1_1") (pintype "passive"))
      (node (ref "C5") (pin "1") (pinfunction "1_1") (pintype "passive"))
      (node (ref "C50") (pin "1") (pinfunction "1_1") (pintype "passive"))
      (node (ref "C51") (pin "1") (pinfunction "1_1") (pintype "passive"))
      (node (ref "C57") (pin "1") (pinfunction "1_1") (pintype "passive"))
      (node (ref "C58") (pin "1") (pinfunction "1_1") (pintype "passive"))
      (node (ref "C63") (pin "1") (pinfunction "1_1") (pintype "passive"))
      (node (ref "C64") (pin "1") (pinfunction "1_1") (pintype "passive"))
      (node (ref "C69") (pin "1") (pinfunction "1_1") (pintype "passive"))
      (node (ref "C70") (pin "1") (pinfunction "1_1") (pintype "passive"))
      (node (ref "C74") (pin "1") (pinfunction "1_1") (pintype "passive"))
      (node (ref "C75") (pin "1") (pinfunction "1_1") (pintype "passive"))
      (node (ref "C80") (pin "1") (pinfunction "1_1") (pintype "passive"))
      (node (ref "C81") (pin "1") (pinfunction "1_1") (pintype "passive"))
      (node (ref "C86") (pin "1") (pinfunction "1_1") (pintype "passive"))
      (node (ref "C87") (pin "1") (pinfunction "1_1") (pintype "passive"))
      (node (ref "C9") (pin "1") (pinfunction "1_1") (pintype "passive"))
      (node (ref "C92") (pin "1") (pinfunction "1_1") (pintype "passive"))
      (node (ref "C93") (pin "1") (pinfunction "1_1") (pintype "passive"))
      (node (ref "C94") (pin "1") (pinfunction "1_1") (pintype "passive"))
      (node (ref "C95") (pin "1") (pinfunction "1_1") (pintype "passive"))
      (node (ref "U1") (pin "3") (pinfunction "VIN_3") (pintype "power_in"))
      (node (ref "U10") (pin "3") (pinfunction "VIN_3") (pintype "power_in"))
      (node (ref "U11") (pin "3") (pinfunction "VIN_3") (pintype "power_in"))
      (node (ref "U11") (pin "5") (pinfunction "EN_5") (pintype "input"))
      (node (ref "U12") (pin "3") (pinfunction "VIN_3") (pintype "power_in"))
      (node (ref "U12") (pin "5") (pinfunction "EN_5") (pintype "input"))
      (node (ref "U13") (pin "3") (pinfunction "VIN_3") (pintype "power_in"))
      (node (ref "U14") (pin "3") (pinfunction "VIN_3") (pintype "power_in"))
      (node (ref "U15") (pin "3") (pinfunction "VIN_3") (pintype "power_in"))
      (node (ref "U16") (pin "3") (pinfunction "VIN_3") (pintype "power_in"))
      (node (ref "U17") (pin "3") (pinfunction "VIN_3") (pintype "power_in"))
      (node (ref "U2") (pin "3") (pinfunction "VIN_3") (pintype "power_in"))
      (node (ref "U24") (pin "3") (pinfunction "VIN_3") (pintype "power_in"))
      (node (ref "U24") (pin "5") (pinfunction "EN_5") (pintype "input"))
      (node (ref "U26") (pin "3") (pinfunction "VIN_3") (pintype "power_in"))
      (node (ref "U26") (pin "5") (pinfunction "EN_5") (pintype "input"))
      (node (ref "U28") (pin "3") (pinfunction "VIN_3") (pintype "power_in"))
      (node (ref "U28") (pin "5") (pinfunction "EN_5") (pintype "input"))
      (node (ref "U3") (pin "3") (pinfunction "VIN_3") (pintype "power_in"))
      (node (ref "U3") (pin "5") (pinfunction "EN_5") (pintype "input"))
      (node (ref "U30") (pin "7") (pinfunction "EN_7") (pintype "input"))
      (node (ref "U30") (pin "8") (pinfunction "VIN_8") (pintype "input"))
      (node (ref "U31") (pin "3") (pinfunction "VIN_3") (pintype "power_in"))
      (node (ref "U31") (pin "5") (pinfunction "EN_5") (pintype "input"))
      (node (ref "U33") (pin "3") (pinfunction "VIN_3") (pintype "power_in"))
      (node (ref "U33") (pin "5") (pinfunction "EN_5") (pintype "input"))
      (node (ref "U4") (pin "3") (pinfunction "VIN_3") (pintype "power_in"))
      (node (ref "U6") (pin "3") (pinfunction "VIN_3") (pintype "power_in"))
      (node (ref "U7") (pin "3") (pinfunction "VIN_3") (pintype "power_in"))
      (node (ref "U8") (pin "3") (pinfunction "VIN_3") (pintype "power_in"))
      (node (ref "U9") (pin "3") (pinfunction "VIN_3") (pintype "power_in"))
      (node (ref "U9") (pin "5") (pinfunction "EN_5") (pintype "input"))
      (node (ref "X1") (pin "1") (pinfunction "KL_1") (pintype "passive"))
    )
    (net (code "51") (name "GND") (class "Default")
      (node (ref "C10") (pin "2") (pinfunction "2_2") (pintype "passive"))
      (node (ref "C101") (pin "1") (pinfunction "+_1") (pintype "bidirectional"))
      (node (ref "C103") (pin "1") (pinfunction "+_1") (pintype "bidirectional"))
      (node (ref "C105") (pin "1") (pinfunction "+_1") (pintype "bidirectional"))
      (node (ref "C106") (pin "1") (pinfunction "1_1") (pintype "passive"))
      (node (ref "C107") (pin "1") (pinfunction "1_1") (pintype "passive"))
      (node (ref "C108") (pin "1") (pinfunction "1_1") (pintype "passive"))
      (node (ref "C11") (pin "2") (pinfunction "2_2") (pintype "passive"))
      (node (ref "C110") (pin "2") (pinfunction "2_2") (pintype "passive"))
      (node (ref "C111") (pin "2") (pinfunction "2_2") (pintype "passive"))
      (node (ref "C112") (pin "2") (pinfunction "2_2") (pintype "passive"))
      (node (ref "C113") (pin "2") (pinfunction "2_2") (pintype "passive"))
      (node (ref "C114") (pin "1") (pinfunction "1_1") (pintype "passive"))
      (node (ref "C115") (pin "1") (pinfunction "1_1") (pintype "passive"))
      (node (ref "C116") (pin "1") (pinfunction "1_1") (pintype "passive"))
      (node (ref "C117") (pin "1") (pinfunction "1_1") (pintype "passive"))
      (node (ref "C118") (pin "1") (pinfunction "1_1") (pintype "passive"))
      (node (ref "C120") (pin "2") (pinfunction "2_2") (pintype "passive"))
      (node (ref "C121") (pin "2") (pinfunction "2_2") (pintype "passive"))
      (node (ref "C122") (pin "2") (pinfunction "2_2") (pintype "passive"))
      (node (ref "C123") (pin "2") (pinfunction "2_2") (pintype "passive"))
      (node (ref "C124") (pin "1") (pinfunction "1_1") (pintype "passive"))
      (node (ref "C125") (pin "1") (pinfunction "1_1") (pintype "passive"))
      (node (ref "C126") (pin "1") (pinfunction "1_1") (pintype "passive"))
      (node (ref "C127") (pin "1") (pinfunction "1_1") (pintype "passive"))
      (node (ref "C128") (pin "1") (pinfunction "1_1") (pintype "passive"))
      (node (ref "C13") (pin "2") (pinfunction "2_2") (pintype "passive"))
      (node (ref "C130") (pin "2") (pinfunction "2_2") (pintype "passive"))
      (node (ref "C131") (pin "2") (pinfunction "2_2") (pintype "passive"))
      (node (ref "C132") (pin "2") (pinfunction "2_2") (pintype "passive"))
      (node (ref "C133") (pin "2") (pinfunction "2_2") (pintype "passive"))
      (node (ref "C134") (pin "1") (pinfunction "1_1") (pintype "passive"))
      (node (ref "C135") (pin "1") (pinfunction "1_1") (pintype "passive"))
      (node (ref "C136") (pin "1") (pinfunction "1_1") (pintype "passive"))
      (node (ref "C137") (pin "1") (pinfunction "1_1") (pintype "passive"))
      (node (ref "C138") (pin "1") (pinfunction "1_1") (pintype "passive"))
      (node (ref "C139") (pin "1") (pinfunction "1_1") (pintype "passive"))
      (node (ref "C14") (pin "2") (pinfunction "2_2") (pintype "passive"))
      (node (ref "C140") (pin "1") (pinfunction "1_1") (pintype "passive"))
      (node (ref "C141") (pin "1") (pinfunction "1_1") (pintype "passive"))
      (node (ref "C142") (pin "1") (pinfunction "1_1") (pintype "passive"))
      (node (ref "C143") (pin "1") (pinfunction "1_1") (pintype "passive"))
      (node (ref "C145") (pin "2") (pinfunction "2_2") (pintype "passive"))
      (node (ref "C146") (pin "2") (pinfunction "2_2") (pintype "passive"))
      (node (ref "C147") (pin "2") (pinfunction "2_2") (pintype "passive"))
      (node (ref "C148") (pin "2") (pinfunction "2_2") (pintype "passive"))
      (node (ref "C149") (pin "2") (pinfunction "2_2") (pintype "passive"))
      (node (ref "C15") (pin "2") (pinfunction "2_2") (pintype "passive"))
      (node (ref "C151") (pin "2") (pinfunction "2_2") (pintype "passive"))
      (node (ref "C152") (pin "2") (pinfunction "2_2") (pintype "passive"))
      (node (ref "C153") (pin "2") (pinfunction "2_2") (pintype "passive"))
      (node (ref "C155") (pin "2") (pinfunction "2_2") (pintype "passive"))
      (node (ref "C156") (pin "2") (pinfunction "2_2") (pintype "passive"))
      (node (ref "C157") (pin "2") (pinfunction "2_2") (pintype "passive"))
      (node (ref "C158") (pin "2") (pinfunction "2_2") (pintype "passive"))
      (node (ref "C159") (pin "2") (pinfunction "2_2") (pintype "passive"))
      (node (ref "C16") (pin "2") (pinfunction "2_2") (pintype "passive"))
      (node (ref "C161") (pin "2") (pinfunction "2_2") (pintype "passive"))
      (node (ref "C162") (pin "2") (pinfunction "2_2") (pintype "passive"))
      (node (ref "C163") (pin "2") (pinfunction "2_2") (pintype "passive"))
      (node (ref "C17") (pin "2") (pinfunction "2_2") (pintype "passive"))
      (node (ref "C19") (pin "2") (pinfunction "2_2") (pintype "passive"))
      (node (ref "C2") (pin "2") (pinfunction "2_2") (pintype "passive"))
      (node (ref "C20") (pin "2") (pinfunction "2_2") (pintype "passive"))
      (node (ref "C21") (pin "2") (pinfunction "2_2") (pintype "passive"))
      (node (ref "C22") (pin "2") (pinfunction "2_2") (pintype "passive"))
      (node (ref "C23") (pin "2") (pinfunction "2_2") (pintype "passive"))
      (node (ref "C24") (pin "1") (pinfunction "1_1") (pintype "passive"))
      (node (ref "C25") (pin "1") (pinfunction "1_1") (pintype "passive"))
      (node (ref "C26") (pin "1") (pinfunction "1_1") (pintype "passive"))
      (node (ref "C27") (pin "1") (pinfunction "1_1") (pintype "passive"))
      (node (ref "C28") (pin "1") (pinfunction "1_1") (pintype "passive"))
      (node (ref "C3") (pin "2") (pinfunction "2_2") (pintype "passive"))
      (node (ref "C31") (pin "2") (pinfunction "2_2") (pintype "passive"))
      (node (ref "C32") (pin "2") (pinfunction "2_2") (pintype "passive"))
      (node (ref "C33") (pin "2") (pinfunction "2_2") (pintype "passive"))
      (node (ref "C34") (pin "2") (pinfunction "2_2") (pintype "passive"))
      (node (ref "C35") (pin "2") (pinfunction "2_2") (pintype "passive"))
      (node (ref "C37") (pin "2") (pinfunction "2_2") (pintype "passive"))
      (node (ref "C38") (pin "2") (pinfunction "2_2") (pintype "passive"))
      (node (ref "C39") (pin "2") (pinfunction "2_2") (pintype "passive"))
      (node (ref "C4") (pin "2") (pinfunction "2_2") (pintype "passive"))
      (node (ref "C40") (pin "2") (pinfunction "2_2") (pintype "passive"))
      (node (ref "C41") (pin "2") (pinfunction "2_2") (pintype "passive"))
      (node (ref "C43") (pin "2") (pinfunction "2_2") (pintype "passive"))
      (node (ref "C44") (pin "2") (pinfunction "2_2") (pintype "passive"))
      (node (ref "C45") (pin "2") (pinfunction "2_2") (pintype "passive"))
      (node (ref "C46") (pin "2") (pinfunction "2_2") (pintype "passive"))
      (node (ref "C47") (pin "2") (pinfunction "2_2") (pintype "passive"))
      (node (ref "C48") (pin "2") (pinfunction "2_2") (pintype "passive"))
      (node (ref "C49") (pin "2") (pinfunction "2_2") (pintype "passive"))
      (node (ref "C5") (pin "2") (pinfunction "2_2") (pintype "passive"))
      (node (ref "C50") (pin "2") (pinfunction "2_2") (pintype "passive"))
      (node (ref "C51") (pin "2") (pinfunction "2_2") (pintype "passive"))
      (node (ref "C52") (pin "1") (pinfunction "1_1") (pintype "passive"))
      (node (ref "C53") (pin "1") (pinfunction "1_1") (pintype "passive"))
      (node (ref "C55") (pin "2") (pinfunction "2_2") (pintype "passive"))
      (node (ref "C56") (pin "2") (pinfunction "2_2") (pintype "passive"))
      (node (ref "C57") (pin "2") (pinfunction "2_2") (pintype "passive"))
      (node (ref "C58") (pin "2") (pinfunction "2_2") (pintype "passive"))
      (node (ref "C59") (pin "2") (pinfunction "2_2") (pintype "passive"))
      (node (ref "C61") (pin "2") (pinfunction "2_2") (pintype "passive"))
      (node (ref "C62") (pin "2") (pinfunction "2_2") (pintype "passive"))
      (node (ref "C63") (pin "2") (pinfunction "2_2") (pintype "passive"))
      (node (ref "C64") (pin "2") (pinfunction "2_2") (pintype "passive"))
      (node (ref "C65") (pin "2") (pinfunction "2_2") (pintype "passive"))
      (node (ref "C67") (pin "2") (pinfunction "2_2") (pintype "passive"))
      (node (ref "C68") (pin "2") (pinfunction "2_2") (pintype "passive"))
      (node (ref "C69") (pin "2") (pinfunction "2_2") (pintype "passive"))
      (node (ref "C7") (pin "2") (pinfunction "2_2") (pintype "passive"))
      (node (ref "C70") (pin "2") (pinfunction "2_2") (pintype "passive"))
      (node (ref "C72") (pin "2") (pinfunction "2_2") (pintype "passive"))
      (node (ref "C73") (pin "2") (pinfunction "2_2") (pintype "passive"))
      (node (ref "C74") (pin "2") (pinfunction "2_2") (pintype "passive"))
      (node (ref "C75") (pin "2") (pinfunction "2_2") (pintype "passive"))
      (node (ref "C78") (pin "2") (pinfunction "2_2") (pintype "passive"))
      (node (ref "C79") (pin "2") (pinfunction "2_2") (pintype "passive"))
      (node (ref "C8") (pin "2") (pinfunction "2_2") (pintype "passive"))
      (node (ref "C80") (pin "2") (pinfunction "2_2") (pintype "passive"))
      (node (ref "C81") (pin "2") (pinfunction "2_2") (pintype "passive"))
      (node (ref "C82") (pin "2") (pinfunction "2_2") (pintype "passive"))
      (node (ref "C84") (pin "2") (pinfunction "2_2") (pintype "passive"))
      (node (ref "C85") (pin "2") (pinfunction "2_2") (pintype "passive"))
      (node (ref "C86") (pin "2") (pinfunction "2_2") (pintype "passive"))
      (node (ref "C87") (pin "2") (pinfunction "2_2") (pintype "passive"))
      (node (ref "C88") (pin "2") (pinfunction "2_2") (pintype "passive"))
      (node (ref "C9") (pin "2") (pinfunction "2_2") (pintype "passive"))
      (node (ref "C90") (pin "2") (pinfunction "2_2") (pintype "passive"))
      (node (ref "C91") (pin "2") (pinfunction "2_2") (pintype "passive"))
      (node (ref "C92") (pin "2") (pinfunction "2_2") (pintype "passive"))
      (node (ref "C93") (pin "2") (pinfunction "2_2") (pintype "passive"))
      (node (ref "C94") (pin "2") (pinfunction "2_2") (pintype "passive"))
      (node (ref "C95") (pin "2") (pinfunction "2_2") (pintype "passive"))
      (node (ref "C97") (pin "1") (pinfunction "+_1") (pintype "bidirectional"))
      (node (ref "C99") (pin "1") (pinfunction "+_1") (pintype "bidirectional"))
      (node (ref "R10") (pin "1") (pinfunction "1_1") (pintype "passive"))
      (node (ref "R12") (pin "1") (pinfunction "1_1") (pintype "passive"))
      (node (ref "R14") (pin "1") (pinfunction "1_1") (pintype "passive"))
      (node (ref "R16") (pin "1") (pinfunction "1_1") (pintype "passive"))
      (node (ref "R18") (pin "1") (pinfunction "1_1") (pintype "passive"))
      (node (ref "R2") (pin "1") (pinfunction "1_1") (pintype "passive"))
      (node (ref "R20") (pin "1") (pinfunction "1_1") (pintype "passive"))
      (node (ref "R22") (pin "1") (pinfunction "1_1") (pintype "passive"))
      (node (ref "R24") (pin "1") (pinfunction "1_1") (pintype "passive"))
      (node (ref "R26") (pin "1") (pinfunction "1_1") (pintype "passive"))
      (node (ref "R28") (pin "1") (pinfunction "1_1") (pintype "passive"))
      (node (ref "R30") (pin "1") (pinfunction "1_1") (pintype "passive"))
      (node (ref "R32") (pin "1") (pinfunction "1_1") (pintype "passive"))
      (node (ref "R34") (pin "1") (pinfunction "1_1") (pintype "passive"))
      (node (ref "R36") (pin "1") (pinfunction "1_1") (pintype "passive"))
      (node (ref "R38") (pin "1") (pinfunction "1_1") (pintype "passive"))
      (node (ref "R4") (pin "1") (pinfunction "1_1") (pintype "passive"))
      (node (ref "R40") (pin "1") (pinfunction "1_1") (pintype "passive"))
      (node (ref "R42") (pin "1") (pinfunction "1_1") (pintype "passive"))
      (node (ref "R44") (pin "1") (pinfunction "1_1") (pintype "passive"))
      (node (ref "R46") (pin "1") (pinfunction "1_1") (pintype "passive"))
      (node (ref "R48") (pin "1") (pinfunction "1_1") (pintype "passive"))
      (node (ref "R50") (pin "1") (pinfunction "1_1") (pintype "passive"))
      (node (ref "R52") (pin "1") (pinfunction "1_1") (pintype "passive"))
      (node (ref "R54") (pin "1") (pinfunction "1_1") (pintype "passive"))
      (node (ref "R56") (pin "1") (pinfunction "1_1") (pintype "passive"))
      (node (ref "R58") (pin "1") (pinfunction "1_1") (pintype "passive"))
      (node (ref "R6") (pin "1") (pinfunction "1_1") (pintype "passive"))
      (node (ref "R8") (pin "1") (pinfunction "1_1") (pintype "passive"))
      (node (ref "SV1") (pin "12") (pinfunction "12_12") (pintype "passive"))
      (node (ref "SV1") (pin "14") (pinfunction "14_14") (pintype "passive"))
      (node (ref "SV1") (pin "16") (pinfunction "16_16") (pintype "passive"))
      (node (ref "SV1") (pin "18") (pinfunction "18_18") (pintype "passive"))
      (node (ref "SV1") (pin "20") (pinfunction "20_20") (pintype "passive"))
      (node (ref "U1") (pin "1") (pinfunction "GND_1") (pintype "power_in"))
      (node (ref "U10") (pin "1") (pinfunction "GND_1") (pintype "power_in"))
      (node (ref "U11") (pin "1") (pinfunction "GND_1") (pintype "power_in"))
      (node (ref "U12") (pin "1") (pinfunction "GND_1") (pintype "power_in"))
      (node (ref "U13") (pin "1") (pinfunction "GND_1") (pintype "power_in"))
      (node (ref "U14") (pin "1") (pinfunction "GND_1") (pintype "power_in"))
      (node (ref "U15") (pin "1") (pinfunction "GND_1") (pintype "power_in"))
      (node (ref "U16") (pin "1") (pinfunction "GND_1") (pintype "power_in"))
      (node (ref "U17") (pin "1") (pinfunction "GND_1") (pintype "power_in"))
      (node (ref "U18") (pin "3") (pinfunction "GND_3") (pintype "passive"))
      (node (ref "U18") (pin "6") (pinfunction "LV_6") (pintype "passive"))
      (node (ref "U19") (pin "3") (pinfunction "GND_3") (pintype "passive"))
      (node (ref "U19") (pin "6") (pinfunction "LV_6") (pintype "passive"))
      (node (ref "U2") (pin "1") (pinfunction "GND_1") (pintype "power_in"))
      (node (ref "U20") (pin "3") (pinfunction "GND_3") (pintype "passive"))
      (node (ref "U20") (pin "6") (pinfunction "LV_6") (pintype "passive"))
      (node (ref "U21") (pin "3") (pinfunction "GND_3") (pintype "passive"))
      (node (ref "U21") (pin "6") (pinfunction "LV_6") (pintype "passive"))
      (node (ref "U22") (pin "3") (pinfunction "GND_3") (pintype "passive"))
      (node (ref "U22") (pin "6") (pinfunction "LV_6") (pintype "passive"))
      (node (ref "U23") (pin "4") (pinfunction "GND_4") (pintype "passive"))
      (node (ref "U23") (pin "9") (pinfunction "EPAD_9") (pintype "passive"))
      (node (ref "U24") (pin "1") (pinfunction "GND_1") (pintype "power_in"))
      (node (ref "U25") (pin "4") (pinfunction "GND_4") (pintype "passive"))
      (node (ref "U25") (pin "9") (pinfunction "EPAD_9") (pintype "passive"))
      (node (ref "U26") (pin "1") (pinfunction "GND_1") (pintype "power_in"))
      (node (ref "U27") (pin "4") (pinfunction "GND_4") (pintype "passive"))
      (node (ref "U27") (pin "9") (pinfunction "EPAD_9") (pintype "passive"))
      (node (ref "U28") (pin "1") (pinfunction "GND_1") (pintype "power_in"))
      (node (ref "U29") (pin "4") (pinfunction "GND_4") (pintype "passive"))
      (node (ref "U29") (pin "9") (pinfunction "EPAD_9") (pintype "passive"))
      (node (ref "U3") (pin "1") (pinfunction "GND_1") (pintype "power_in"))
      (node (ref "U30") (pin "4") (pinfunction "GND_4") (pintype "passive"))
      (node (ref "U30") (pin "9") (pinfunction "EPAD_9") (pintype "passive"))
      (node (ref "U31") (pin "1") (pinfunction "GND_1") (pintype "power_in"))
      (node (ref "U32") (pin "18") (pinfunction "GND_18") (pintype "power_in"))
      (node (ref "U32") (pin "21") (pinfunction "EPAD_21") (pintype "passive"))
      (node (ref "U32") (pin "8") (pinfunction "GND_2_8") (pintype "power_in"))
      (node (ref "U33") (pin "1") (pinfunction "GND_1") (pintype "power_in"))
      (node (ref "U34") (pin "18") (pinfunction "GND_18") (pintype "power_in"))
      (node (ref "U34") (pin "21") (pinfunction "EPAD_21") (pintype "passive"))
      (node (ref "U34") (pin "8") (pinfunction "GND_2_8") (pintype "power_in"))
      (node (ref "U4") (pin "1") (pinfunction "GND_1") (pintype "power_in"))
      (node (ref "U5") (pin "4") (pinfunction "GND_4") (pintype "passive"))
      (node (ref "U5") (pin "9") (pinfunction "EPAD_9") (pintype "passive"))
      (node (ref "U6") (pin "1") (pinfunction "GND_1") (pintype "power_in"))
      (node (ref "U7") (pin "1") (pinfunction "GND_1") (pintype "power_in"))
      (node (ref "U8") (pin "1") (pinfunction "GND_1") (pintype "power_in"))
      (node (ref "U9") (pin "1") (pinfunction "GND_1") (pintype "power_in"))
      (node (ref "X1") (pin "2") (pinfunction "KL_2") (pintype "passive"))
      (node (ref "X10") (pin "2") (pinfunction "S_2") (pintype "passive"))
      (node (ref "X11") (pin "2") (pinfunction "S_2") (pintype "passive"))
      (node (ref "X12") (pin "2") (pinfunction "S_2") (pintype "passive"))
      (node (ref "X13") (pin "2") (pinfunction "S_2") (pintype "passive"))
      (node (ref "X14") (pin "2") (pinfunction "S_2") (pintype "passive"))
      (node (ref "X15") (pin "2") (pinfunction "S_2") (pintype "passive"))
      (node (ref "X16") (pin "2") (pinfunction "S_2") (pintype "passive"))
      (node (ref "X17") (pin "2") (pinfunction "S_2") (pintype "passive"))
      (node (ref "X18") (pin "2") (pinfunction "S_2") (pintype "passive"))
      (node (ref "X19") (pin "2") (pinfunction "S_2") (pintype "passive"))
      (node (ref "X2") (pin "2") (pinfunction "S_2") (pintype "passive"))
      (node (ref "X20") (pin "2") (pinfunction "S_2") (pintype "passive"))
      (node (ref "X21") (pin "2") (pinfunction "S_2") (pintype "passive"))
      (node (ref "X22") (pin "2") (pinfunction "S_2") (pintype "passive"))
      (node (ref "X23") (pin "2") (pinfunction "S_2") (pintype "passive"))
      (node (ref "X24") (pin "2") (pinfunction "S_2") (pintype "passive"))
      (node (ref "X25") (pin "2") (pinfunction "S_2") (pintype "passive"))
      (node (ref "X26") (pin "2") (pinfunction "S_2") (pintype "passive"))
      (node (ref "X27") (pin "2") (pinfunction "S_2") (pintype "passive"))
      (node (ref "X28") (pin "2") (pinfunction "S_2") (pintype "passive"))
      (node (ref "X29") (pin "2") (pinfunction "S_2") (pintype "passive"))
      (node (ref "X3") (pin "2") (pinfunction "S_2") (pintype "passive"))
      (node (ref "X30") (pin "2") (pinfunction "S_2") (pintype "passive"))
      (node (ref "X31") (pin "2") (pinfunction "S_2") (pintype "passive"))
      (node (ref "X32") (pin "2") (pinfunction "S_2") (pintype "passive"))
      (node (ref "X33") (pin "2") (pinfunction "S_2") (pintype "passive"))
      (node (ref "X34") (pin "2") (pinfunction "S_2") (pintype "passive"))
      (node (ref "X35") (pin "2") (pinfunction "S_2") (pintype "passive"))
      (node (ref "X4") (pin "2") (pinfunction "S_2") (pintype "passive"))
      (node (ref "X5") (pin "2") (pinfunction "S_2") (pintype "passive"))
      (node (ref "X6") (pin "2") (pinfunction "S_2") (pintype "passive"))
      (node (ref "X7") (pin "2") (pinfunction "S_2") (pintype "passive"))
      (node (ref "X8") (pin "2") (pinfunction "S_2") (pintype "passive"))
      (node (ref "X9") (pin "2") (pinfunction "S_2") (pintype "passive"))
    )
    (net (code "52") (name "Net-(C96-+)") (class "Default")
      (node (ref "C96") (pin "1") (pinfunction "+_1") (pintype "bidirectional"))
      (node (ref "U18") (pin "2") (pinfunction "C1+_2") (pintype "passive"))
    )
    (net (code "53") (name "Net-(C96--)") (class "Default")
      (node (ref "C96") (pin "2") (pinfunction "-_2") (pintype "bidirectional"))
      (node (ref "U18") (pin "4") (pinfunction "C1-_4") (pintype "passive"))
    )
    (net (code "54") (name "Net-(C98-+)") (class "Default")
      (node (ref "C98") (pin "1") (pinfunction "+_1") (pintype "bidirectional"))
      (node (ref "U19") (pin "2") (pinfunction "C1+_2") (pintype "passive"))
    )
    (net (code "55") (name "Net-(C98--)") (class "Default")
      (node (ref "C98") (pin "2") (pinfunction "-_2") (pintype "bidirectional"))
      (node (ref "U19") (pin "4") (pinfunction "C1-_4") (pintype "passive"))
    )
    (net (code "56") (name "Net-(C100-+)") (class "Default")
      (node (ref "C100") (pin "1") (pinfunction "+_1") (pintype "bidirectional"))
      (node (ref "U20") (pin "2") (pinfunction "C1+_2") (pintype "passive"))
    )
    (net (code "57") (name "Net-(C100--)") (class "Default")
      (node (ref "C100") (pin "2") (pinfunction "-_2") (pintype "bidirectional"))
      (node (ref "U20") (pin "4") (pinfunction "C1-_4") (pintype "passive"))
    )
    (net (code "58") (name "Net-(C102-+)") (class "Default")
      (node (ref "C102") (pin "1") (pinfunction "+_1") (pintype "bidirectional"))
      (node (ref "U21") (pin "2") (pinfunction "C1+_2") (pintype "passive"))
    )
    (net (code "59") (name "Net-(C102--)") (class "Default")
      (node (ref "C102") (pin "2") (pinfunction "-_2") (pintype "bidirectional"))
      (node (ref "U21") (pin "4") (pinfunction "C1-_4") (pintype "passive"))
    )
    (net (code "60") (name "Net-(C104-+)") (class "Default")
      (node (ref "C104") (pin "1") (pinfunction "+_1") (pintype "bidirectional"))
      (node (ref "U22") (pin "2") (pinfunction "C1+_2") (pintype "passive"))
    )
    (net (code "61") (name "Net-(C104--)") (class "Default")
      (node (ref "C104") (pin "2") (pinfunction "-_2") (pintype "bidirectional"))
      (node (ref "U22") (pin "4") (pinfunction "C1-_4") (pintype "passive"))
    )
    (net (code "62") (name "Net-(U1-SW)") (class "Default")
      (node (ref "C1") (pin "2") (pinfunction "2_2") (pintype "passive"))
      (node (ref "U$1") (pin "2") (pinfunction "2_2") (pintype "passive"))
      (node (ref "U1") (pin "2") (pinfunction "SW_2") (pintype "power_in"))
    )
    (net (code "63") (name "Net-(U1-VBST)") (class "Default")
      (node (ref "C1") (pin "1") (pinfunction "1_1") (pintype "passive"))
      (node (ref "U1") (pin "6") (pinfunction "VBST_6") (pintype "power_in"))
    )
    (net (code "64") (name "Net-(U1-VFB)") (class "Default")
      (node (ref "R1") (pin "1") (pinfunction "1_1") (pintype "passive"))
      (node (ref "R2") (pin "2") (pinfunction "2_2") (pintype "passive"))
      (node (ref "U1") (pin "4") (pinfunction "VFB_4") (pintype "input"))
    )
    (net (code "65") (name "Net-(U2-SW)") (class "Default")
      (node (ref "C6") (pin "2") (pinfunction "2_2") (pintype "passive"))
      (node (ref "U$2") (pin "2") (pinfunction "2_2") (pintype "passive"))
      (node (ref "U2") (pin "2") (pinfunction "SW_2") (pintype "power_in"))
    )
    (net (code "66") (name "Net-(U2-VBST)") (class "Default")
      (node (ref "C6") (pin "1") (pinfunction "1_1") (pintype "passive"))
      (node (ref "U2") (pin "6") (pinfunction "VBST_6") (pintype "power_in"))
    )
    (net (code "67") (name "Net-(U2-VFB)") (class "Default")
      (node (ref "R3") (pin "1") (pinfunction "1_1") (pintype "passive"))
      (node (ref "R4") (pin "2") (pinfunction "2_2") (pintype "passive"))
      (node (ref "U2") (pin "4") (pinfunction "VFB_4") (pintype "input"))
    )
    (net (code "68") (name "Net-(U3-SW)") (class "Default")
      (node (ref "C12") (pin "2") (pinfunction "2_2") (pintype "passive"))
      (node (ref "U$3") (pin "2") (pinfunction "2_2") (pintype "passive"))
      (node (ref "U3") (pin "2") (pinfunction "SW_2") (pintype "power_in"))
    )
    (net (code "69") (name "Net-(U3-VBST)") (class "Default")
      (node (ref "C12") (pin "1") (pinfunction "1_1") (pintype "passive"))
      (node (ref "U3") (pin "6") (pinfunction "VBST_6") (pintype "power_in"))
    )
    (net (code "70") (name "Net-(U3-VFB)") (class "Default")
      (node (ref "R5") (pin "1") (pinfunction "1_1") (pintype "passive"))
      (node (ref "R6") (pin "2") (pinfunction "2_2") (pintype "passive"))
      (node (ref "U3") (pin "4") (pinfunction "VFB_4") (pintype "input"))
    )
    (net (code "71") (name "Net-(U4-SW)") (class "Default")
      (node (ref "C18") (pin "2") (pinfunction "2_2") (pintype "passive"))
      (node (ref "U$4") (pin "2") (pinfunction "2_2") (pintype "passive"))
      (node (ref "U4") (pin "2") (pinfunction "SW_2") (pintype "power_in"))
    )
    (net (code "72") (name "Net-(U4-VBST)") (class "Default")
      (node (ref "C18") (pin "1") (pinfunction "1_1") (pintype "passive"))
      (node (ref "U4") (pin "6") (pinfunction "VBST_6") (pintype "power_in"))
    )
    (net (code "73") (name "Net-(U4-VFB)") (class "Default")
      (node (ref "R7") (pin "1") (pinfunction "1_1") (pintype "passive"))
      (node (ref "R8") (pin "2") (pinfunction "2_2") (pintype "passive"))
      (node (ref "U4") (pin "4") (pinfunction "VFB_4") (pintype "input"))
    )
    (net (code "74") (name "Net-(U5-BYP)") (class "Default")
      (node (ref "C26") (pin "2") (pinfunction "2_2") (pintype "passive"))
      (node (ref "U5") (pin "3") (pinfunction "BYP_3") (pintype "passive"))
    )
    (net (code "75") (name "Net-(U5-REF)") (class "Default")
      (node (ref "C27") (pin "2") (pinfunction "2_2") (pintype "passive"))
      (node (ref "R9") (pin "2") (pinfunction "2_2") (pintype "passive"))
      (node (ref "U5") (pin "6") (pinfunction "REF_6") (pintype "output"))
    )
    (net (code "76") (name "Net-(U5-REF_SENSE)") (class "Default")
      (node (ref "R10") (pin "2") (pinfunction "2_2") (pintype "passive"))
      (node (ref "R9") (pin "1") (pinfunction "1_1") (pintype "passive"))
      (node (ref "U5") (pin "5") (pinfunction "REF_SENSE_5") (pintype "passive"))
    )
    (net (code "77") (name "Net-(U5-VREG)") (class "Default")
      (node (ref "C24") (pin "2") (pinfunction "2_2") (pintype "passive"))
      (node (ref "U5") (pin "1") (pinfunction "VREG_1") (pintype "power_in"))
    )
    (net (code "78") (name "Net-(U6-SW)") (class "Default")
      (node (ref "C30") (pin "2") (pinfunction "2_2") (pintype "passive"))
      (node (ref "U$6") (pin "2") (pinfunction "2_2") (pintype "passive"))
      (node (ref "U6") (pin "2") (pinfunction "SW_2") (pintype "power_in"))
    )
    (net (code "79") (name "Net-(U6-VBST)") (class "Default")
      (node (ref "C30") (pin "1") (pinfunction "1_1") (pintype "passive"))
      (node (ref "U6") (pin "6") (pinfunction "VBST_6") (pintype "power_in"))
    )
    (net (code "80") (name "Net-(U6-VFB)") (class "Default")
      (node (ref "R11") (pin "1") (pinfunction "1_1") (pintype "passive"))
      (node (ref "R12") (pin "2") (pinfunction "2_2") (pintype "passive"))
      (node (ref "U6") (pin "4") (pinfunction "VFB_4") (pintype "input"))
    )
    (net (code "81") (name "Net-(U7-SW)") (class "Default")
      (node (ref "C36") (pin "2") (pinfunction "2_2") (pintype "passive"))
      (node (ref "U$7") (pin "2") (pinfunction "2_2") (pintype "passive"))
      (node (ref "U7") (pin "2") (pinfunction "SW_2") (pintype "power_in"))
    )
    (net (code "82") (name "Net-(U7-VBST)") (class "Default")
      (node (ref "C36") (pin "1") (pinfunction "1_1") (pintype "passive"))
      (node (ref "U7") (pin "6") (pinfunction "VBST_6") (pintype "power_in"))
    )
    (net (code "83") (name "Net-(U7-VFB)") (class "Default")
      (node (ref "R13") (pin "1") (pinfunction "1_1") (pintype "passive"))
      (node (ref "R14") (pin "2") (pinfunction "2_2") (pintype "passive"))
      (node (ref "U7") (pin "4") (pinfunction "VFB_4") (pintype "input"))
    )
    (net (code "84") (name "Net-(U8-SW)") (class "Default")
      (node (ref "C42") (pin "2") (pinfunction "2_2") (pintype "passive"))
      (node (ref "U$8") (pin "2") (pinfunction "2_2") (pintype "passive"))
      (node (ref "U8") (pin "2") (pinfunction "SW_2") (pintype "power_in"))
    )
    (net (code "85") (name "Net-(U8-VBST)") (class "Default")
      (node (ref "C42") (pin "1") (pinfunction "1_1") (pintype "passive"))
      (node (ref "U8") (pin "6") (pinfunction "VBST_6") (pintype "power_in"))
    )
    (net (code "86") (name "Net-(U8-VFB)") (class "Default")
      (node (ref "R15") (pin "1") (pinfunction "1_1") (pintype "passive"))
      (node (ref "R16") (pin "2") (pinfunction "2_2") (pintype "passive"))
      (node (ref "U8") (pin "4") (pinfunction "VFB_4") (pintype "input"))
    )
    (net (code "87") (name "Net-(U9-SW)") (class "Default")
      (node (ref "C29") (pin "2") (pinfunction "2_2") (pintype "passive"))
      (node (ref "U$5") (pin "2") (pinfunction "2_2") (pintype "passive"))
      (node (ref "U9") (pin "2") (pinfunction "SW_2") (pintype "power_in"))
    )
    (net (code "88") (name "Net-(U9-VBST)") (class "Default")
      (node (ref "C29") (pin "1") (pinfunction "1_1") (pintype "passive"))
      (node (ref "U9") (pin "6") (pinfunction "VBST_6") (pintype "power_in"))
    )
    (net (code "89") (name "Net-(U9-VFB)") (class "Default")
      (node (ref "R17") (pin "1") (pinfunction "1_1") (pintype "passive"))
      (node (ref "R18") (pin "2") (pinfunction "2_2") (pintype "passive"))
      (node (ref "U9") (pin "4") (pinfunction "VFB_4") (pintype "input"))
    )
    (net (code "90") (name "Net-(U10-SW)") (class "Default")
      (node (ref "C54") (pin "2") (pinfunction "2_2") (pintype "passive"))
      (node (ref "U$10") (pin "2") (pinfunction "2_2") (pintype "passive"))
      (node (ref "U10") (pin "2") (pinfunction "SW_2") (pintype "power_in"))
    )
    (net (code "91") (name "Net-(U10-VBST)") (class "Default")
      (node (ref "C54") (pin "1") (pinfunction "1_1") (pintype "passive"))
      (node (ref "U10") (pin "6") (pinfunction "VBST_6") (pintype "power_in"))
    )
    (net (code "92") (name "Net-(U10-VFB)") (class "Default")
      (node (ref "R19") (pin "1") (pinfunction "1_1") (pintype "passive"))
      (node (ref "R20") (pin "2") (pinfunction "2_2") (pintype "passive"))
      (node (ref "U10") (pin "4") (pinfunction "VFB_4") (pintype "input"))
    )
    (net (code "93") (name "Net-(U11-SW)") (class "Default")
      (node (ref "C60") (pin "2") (pinfunction "2_2") (pintype "passive"))
      (node (ref "U$11") (pin "2") (pinfunction "2_2") (pintype "passive"))
      (node (ref "U11") (pin "2") (pinfunction "SW_2") (pintype "power_in"))
    )
    (net (code "94") (name "Net-(U11-VBST)") (class "Default")
      (node (ref "C60") (pin "1") (pinfunction "1_1") (pintype "passive"))
      (node (ref "U11") (pin "6") (pinfunction "VBST_6") (pintype "power_in"))
    )
    (net (code "95") (name "Net-(U11-VFB)") (class "Default")
      (node (ref "R21") (pin "1") (pinfunction "1_1") (pintype "passive"))
      (node (ref "R22") (pin "2") (pinfunction "2_2") (pintype "passive"))
      (node (ref "U11") (pin "4") (pinfunction "VFB_4") (pintype "input"))
    )
    (net (code "96") (name "Net-(U12-SW)") (class "Default")
      (node (ref "C66") (pin "2") (pinfunction "2_2") (pintype "passive"))
      (node (ref "U$12") (pin "2") (pinfunction "2_2") (pintype "passive"))
      (node (ref "U12") (pin "2") (pinfunction "SW_2") (pintype "power_in"))
    )
    (net (code "97") (name "Net-(U12-VBST)") (class "Default")
      (node (ref "C66") (pin "1") (pinfunction "1_1") (pintype "passive"))
      (node (ref "U12") (pin "6") (pinfunction "VBST_6") (pintype "power_in"))
    )
    (net (code "98") (name "Net-(U12-VFB)") (class "Default")
      (node (ref "R23") (pin "1") (pinfunction "1_1") (pintype "passive"))
      (node (ref "R24") (pin "2") (pinfunction "2_2") (pintype "passive"))
      (node (ref "U12") (pin "4") (pinfunction "VFB_4") (pintype "input"))
    )
    (net (code "99") (name "Net-(U13-SW)") (class "Default")
      (node (ref "C71") (pin "2") (pinfunction "2_2") (pintype "passive"))
      (node (ref "U$13") (pin "2") (pinfunction "2_2") (pintype "passive"))
      (node (ref "U13") (pin "2") (pinfunction "SW_2") (pintype "power_in"))
    )
    (net (code "100") (name "Net-(U13-VBST)") (class "Default")
      (node (ref "C71") (pin "1") (pinfunction "1_1") (pintype "passive"))
      (node (ref "U13") (pin "6") (pinfunction "VBST_6") (pintype "power_in"))
    )
    (net (code "101") (name "Net-(U13-VFB)") (class "Default")
      (node (ref "R25") (pin "1") (pinfunction "1_1") (pintype "passive"))
      (node (ref "R26") (pin "2") (pinfunction "2_2") (pintype "passive"))
      (node (ref "U13") (pin "4") (pinfunction "VFB_4") (pintype "input"))
    )
    (net (code "102") (name "Net-(U14-SW)") (class "Default")
      (node (ref "C77") (pin "2") (pinfunction "2_2") (pintype "passive"))
      (node (ref "U$14") (pin "2") (pinfunction "2_2") (pintype "passive"))
      (node (ref "U14") (pin "2") (pinfunction "SW_2") (pintype "power_in"))
    )
    (net (code "103") (name "Net-(U14-VBST)") (class "Default")
      (node (ref "C77") (pin "1") (pinfunction "1_1") (pintype "passive"))
      (node (ref "U14") (pin "6") (pinfunction "VBST_6") (pintype "power_in"))
    )
    (net (code "104") (name "Net-(U14-VFB)") (class "Default")
      (node (ref "R27") (pin "1") (pinfunction "1_1") (pintype "passive"))
      (node (ref "R28") (pin "2") (pinfunction "2_2") (pintype "passive"))
      (node (ref "U14") (pin "4") (pinfunction "VFB_4") (pintype "input"))
    )
    (net (code "105") (name "Net-(U15-SW)") (class "Default")
      (node (ref "C83") (pin "2") (pinfunction "2_2") (pintype "passive"))
      (node (ref "U$15") (pin "2") (pinfunction "2_2") (pintype "passive"))
      (node (ref "U15") (pin "2") (pinfunction "SW_2") (pintype "power_in"))
    )
    (net (code "106") (name "Net-(U15-VBST)") (class "Default")
      (node (ref "C83") (pin "1") (pinfunction "1_1") (pintype "passive"))
      (node (ref "U15") (pin "6") (pinfunction "VBST_6") (pintype "power_in"))
    )
    (net (code "107") (name "Net-(U15-VFB)") (class "Default")
      (node (ref "R29") (pin "1") (pinfunction "1_1") (pintype "passive"))
      (node (ref "R30") (pin "2") (pinfunction "2_2") (pintype "passive"))
      (node (ref "U15") (pin "4") (pinfunction "VFB_4") (pintype "input"))
    )
    (net (code "108") (name "Net-(U16-SW)") (class "Default")
      (node (ref "C89") (pin "2") (pinfunction "2_2") (pintype "passive"))
      (node (ref "U$16") (pin "2") (pinfunction "2_2") (pintype "passive"))
      (node (ref "U16") (pin "2") (pinfunction "SW_2") (pintype "power_in"))
    )
    (net (code "109") (name "Net-(U16-VBST)") (class "Default")
      (node (ref "C89") (pin "1") (pinfunction "1_1") (pintype "passive"))
      (node (ref "U16") (pin "6") (pinfunction "VBST_6") (pintype "power_in"))
    )
    (net (code "110") (name "Net-(U16-VFB)") (class "Default")
      (node (ref "R31") (pin "1") (pinfunction "1_1") (pintype "passive"))
      (node (ref "R32") (pin "2") (pinfunction "2_2") (pintype "passive"))
      (node (ref "U16") (pin "4") (pinfunction "VFB_4") (pintype "input"))
    )
    (net (code "111") (name "Net-(U17-SW)") (class "Default")
      (node (ref "C76") (pin "2") (pinfunction "2_2") (pintype "passive"))
      (node (ref "U$17") (pin "2") (pinfunction "2_2") (pintype "passive"))
      (node (ref "U17") (pin "2") (pinfunction "SW_2") (pintype "power_in"))
    )
    (net (code "112") (name "Net-(U17-VBST)") (class "Default")
      (node (ref "C76") (pin "1") (pinfunction "1_1") (pintype "passive"))
      (node (ref "U17") (pin "6") (pinfunction "VBST_6") (pintype "power_in"))
    )
    (net (code "113") (name "Net-(U17-VFB)") (class "Default")
      (node (ref "R33") (pin "1") (pinfunction "1_1") (pintype "passive"))
      (node (ref "R34") (pin "2") (pinfunction "2_2") (pintype "passive"))
      (node (ref "U17") (pin "4") (pinfunction "VFB_4") (pintype "input"))
    )
    (net (code "114") (name "Net-(U23-BYP)") (class "Default")
      (node (ref "C106") (pin "2") (pinfunction "2_2") (pintype "passive"))
      (node (ref "U23") (pin "3") (pinfunction "BYP_3") (pintype "passive"))
    )
    (net (code "115") (name "Net-(U23-REF)") (class "Default")
      (node (ref "C107") (pin "2") (pinfunction "2_2") (pintype "passive"))
      (node (ref "R35") (pin "2") (pinfunction "2_2") (pintype "passive"))
      (node (ref "U23") (pin "6") (pinfunction "REF_6") (pintype "output"))
    )
    (net (code "116") (name "Net-(U23-REF_SENSE)") (class "Default")
      (node (ref "R35") (pin "1") (pinfunction "1_1") (pintype "passive"))
      (node (ref "R36") (pin "2") (pinfunction "2_2") (pintype "passive"))
      (node (ref "U23") (pin "5") (pinfunction "REF_SENSE_5") (pintype "passive"))
    )
    (net (code "117") (name "Net-(U23-VREG)") (class "Default")
      (node (ref "C52") (pin "2") (pinfunction "2_2") (pintype "passive"))
      (node (ref "U23") (pin "1") (pinfunction "VREG_1") (pintype "power_in"))
    )
    (net (code "118") (name "Net-(U24-SW)") (class "Default")
      (node (ref "C109") (pin "2") (pinfunction "2_2") (pintype "passive"))
      (node (ref "U$9") (pin "2") (pinfunction "2_2") (pintype "passive"))
      (node (ref "U24") (pin "2") (pinfunction "SW_2") (pintype "power_in"))
    )
    (net (code "119") (name "Net-(U24-VBST)") (class "Default")
      (node (ref "C109") (pin "1") (pinfunction "1_1") (pintype "passive"))
      (node (ref "U24") (pin "6") (pinfunction "VBST_6") (pintype "power_in"))
    )
    (net (code "120") (name "Net-(U24-VFB)") (class "Default")
      (node (ref "R37") (pin "1") (pinfunction "1_1") (pintype "passive"))
      (node (ref "R38") (pin "2") (pinfunction "2_2") (pintype "passive"))
      (node (ref "U24") (pin "4") (pinfunction "VFB_4") (pintype "input"))
    )
    (net (code "121") (name "Net-(U25-BYP)") (class "Default")
      (node (ref "C116") (pin "2") (pinfunction "2_2") (pintype "passive"))
      (node (ref "U25") (pin "3") (pinfunction "BYP_3") (pintype "passive"))
    )
    (net (code "122") (name "Net-(U25-REF)") (class "Default")
      (node (ref "C117") (pin "2") (pinfunction "2_2") (pintype "passive"))
      (node (ref "R39") (pin "2") (pinfunction "2_2") (pintype "passive"))
      (node (ref "U25") (pin "6") (pinfunction "REF_6") (pintype "output"))
    )
    (net (code "123") (name "Net-(U25-REF_SENSE)") (class "Default")
      (node (ref "R39") (pin "1") (pinfunction "1_1") (pintype "passive"))
      (node (ref "R40") (pin "2") (pinfunction "2_2") (pintype "passive"))
      (node (ref "U25") (pin "5") (pinfunction "REF_SENSE_5") (pintype "passive"))
    )
    (net (code "124") (name "Net-(U25-VREG)") (class "Default")
      (node (ref "C114") (pin "2") (pinfunction "2_2") (pintype "passive"))
      (node (ref "U25") (pin "1") (pinfunction "VREG_1") (pintype "power_in"))
    )
    (net (code "125") (name "Net-(U26-SW)") (class "Default")
      (node (ref "C119") (pin "2") (pinfunction "2_2") (pintype "passive"))
      (node (ref "U$18") (pin "2") (pinfunction "2_2") (pintype "passive"))
      (node (ref "U26") (pin "2") (pinfunction "SW_2") (pintype "power_in"))
    )
    (net (code "126") (name "Net-(U26-VBST)") (class "Default")
      (node (ref "C119") (pin "1") (pinfunction "1_1") (pintype "passive"))
      (node (ref "U26") (pin "6") (pinfunction "VBST_6") (pintype "power_in"))
    )
    (net (code "127") (name "Net-(U26-VFB)") (class "Default")
      (node (ref "R41") (pin "1") (pinfunction "1_1") (pintype "passive"))
      (node (ref "R42") (pin "2") (pinfunction "2_2") (pintype "passive"))
      (node (ref "U26") (pin "4") (pinfunction "VFB_4") (pintype "input"))
    )
    (net (code "128") (name "Net-(U27-BYP)") (class "Default")
      (node (ref "C126") (pin "2") (pinfunction "2_2") (pintype "passive"))
      (node (ref "U27") (pin "3") (pinfunction "BYP_3") (pintype "passive"))
    )
    (net (code "129") (name "Net-(U27-REF)") (class "Default")
      (node (ref "C127") (pin "2") (pinfunction "2_2") (pintype "passive"))
      (node (ref "R43") (pin "2") (pinfunction "2_2") (pintype "passive"))
      (node (ref "U27") (pin "6") (pinfunction "REF_6") (pintype "output"))
    )
    (net (code "130") (name "Net-(U27-REF_SENSE)") (class "Default")
      (node (ref "R43") (pin "1") (pinfunction "1_1") (pintype "passive"))
      (node (ref "R44") (pin "2") (pinfunction "2_2") (pintype "passive"))
      (node (ref "U27") (pin "5") (pinfunction "REF_SENSE_5") (pintype "passive"))
    )
    (net (code "131") (name "Net-(U27-VREG)") (class "Default")
      (node (ref "C124") (pin "2") (pinfunction "2_2") (pintype "passive"))
      (node (ref "U27") (pin "1") (pinfunction "VREG_1") (pintype "power_in"))
    )
    (net (code "132") (name "Net-(U28-SW)") (class "Default")
      (node (ref "C129") (pin "2") (pinfunction "2_2") (pintype "passive"))
      (node (ref "U$19") (pin "2") (pinfunction "2_2") (pintype "passive"))
      (node (ref "U28") (pin "2") (pinfunction "SW_2") (pintype "power_in"))
    )
    (net (code "133") (name "Net-(U28-VBST)") (class "Default")
      (node (ref "C129") (pin "1") (pinfunction "1_1") (pintype "passive"))
      (node (ref "U28") (pin "6") (pinfunction "VBST_6") (pintype "power_in"))
    )
    (net (code "134") (name "Net-(U28-VFB)") (class "Default")
      (node (ref "R45") (pin "1") (pinfunction "1_1") (pintype "passive"))
      (node (ref "R46") (pin "2") (pinfunction "2_2") (pintype "passive"))
      (node (ref "U28") (pin "4") (pinfunction "VFB_4") (pintype "input"))
    )
    (net (code "135") (name "Net-(U29-BYP)") (class "Default")
      (node (ref "C136") (pin "2") (pinfunction "2_2") (pintype "passive"))
      (node (ref "U29") (pin "3") (pinfunction "BYP_3") (pintype "passive"))
    )
    (net (code "136") (name "Net-(U29-REF)") (class "Default")
      (node (ref "C137") (pin "2") (pinfunction "2_2") (pintype "passive"))
      (node (ref "R47") (pin "2") (pinfunction "2_2") (pintype "passive"))
      (node (ref "U29") (pin "6") (pinfunction "REF_6") (pintype "output"))
    )
    (net (code "137") (name "Net-(U29-REF_SENSE)") (class "Default")
      (node (ref "R47") (pin "1") (pinfunction "1_1") (pintype "passive"))
      (node (ref "R48") (pin "2") (pinfunction "2_2") (pintype "passive"))
      (node (ref "U29") (pin "5") (pinfunction "REF_SENSE_5") (pintype "passive"))
    )
    (net (code "138") (name "Net-(U29-VREG)") (class "Default")
      (node (ref "C134") (pin "2") (pinfunction "2_2") (pintype "passive"))
      (node (ref "U29") (pin "1") (pinfunction "VREG_1") (pintype "power_in"))
    )
    (net (code "139") (name "Net-(U30-BYP)") (class "Default")
      (node (ref "C141") (pin "2") (pinfunction "2_2") (pintype "passive"))
      (node (ref "U30") (pin "3") (pinfunction "BYP_3") (pintype "passive"))
    )
    (net (code "140") (name "Net-(U30-REF)") (class "Default")
      (node (ref "C142") (pin "2") (pinfunction "2_2") (pintype "passive"))
      (node (ref "R49") (pin "2") (pinfunction "2_2") (pintype "passive"))
      (node (ref "U30") (pin "6") (pinfunction "REF_6") (pintype "output"))
    )
    (net (code "141") (name "Net-(U30-REF_SENSE)") (class "Default")
      (node (ref "R49") (pin "1") (pinfunction "1_1") (pintype "passive"))
      (node (ref "R50") (pin "2") (pinfunction "2_2") (pintype "passive"))
      (node (ref "U30") (pin "5") (pinfunction "REF_SENSE_5") (pintype "passive"))
    )
    (net (code "142") (name "Net-(U30-VREG)") (class "Default")
      (node (ref "C139") (pin "2") (pinfunction "2_2") (pintype "passive"))
      (node (ref "U30") (pin "1") (pinfunction "VREG_1") (pintype "power_in"))
    )
    (net (code "143") (name "Net-(U31-SW)") (class "Default")
      (node (ref "C144") (pin "2") (pinfunction "2_2") (pintype "passive"))
      (node (ref "U$20") (pin "2") (pinfunction "2_2") (pintype "passive"))
      (node (ref "U31") (pin "2") (pinfunction "SW_2") (pintype "power_in"))
    )
    (net (code "144") (name "Net-(U31-VBST)") (class "Default")
      (node (ref "C144") (pin "1") (pinfunction "1_1") (pintype "passive"))
      (node (ref "U31") (pin "6") (pinfunction "VBST_6") (pintype "power_in"))
    )
    (net (code "145") (name "Net-(U31-VFB)") (class "Default")
      (node (ref "R51") (pin "1") (pinfunction "1_1") (pintype "passive"))
      (node (ref "R52") (pin "2") (pinfunction "2_2") (pintype "passive"))
      (node (ref "U31") (pin "4") (pinfunction "VFB_4") (pintype "input"))
    )
    (net (code "146") (name "Net-(U32-BIAS)") (class "Default")
      (node (ref "C151") (pin "1") (pinfunction "1_1") (pintype "passive"))
      (node (ref "U32") (pin "12") (pinfunction "BIAS_12") (pintype "input"))
    )
    (net (code "147") (name "Net-(U32-FB)") (class "Default")
      (node (ref "C150") (pin "2") (pinfunction "2_2") (pintype "passive"))
      (node (ref "R53") (pin "1") (pinfunction "1_1") (pintype "passive"))
      (node (ref "R54") (pin "2") (pinfunction "2_2") (pintype "passive"))
      (node (ref "U32") (pin "3") (pinfunction "FB_3") (pintype "input"))
    )
    (net (code "148") (name "Net-(U32-NR{slash}SS)") (class "Default")
      (node (ref "C152") (pin "1") (pinfunction "1_1") (pintype "passive"))
      (node (ref "U32") (pin "13") (pinfunction "NR/SS_13") (pintype "passive"))
    )
    (net (code "149") (name "Net-(U32-SNS)") (class "Default")
      (node (ref "C150") (pin "1") (pinfunction "1_1") (pintype "passive"))
      (node (ref "U32") (pin "2") (pinfunction "SNS_2") (pintype "input"))
    )
    (net (code "150") (name "Net-(U33-SW)") (class "Default")
      (node (ref "C154") (pin "2") (pinfunction "2_2") (pintype "passive"))
      (node (ref "U$21") (pin "2") (pinfunction "2_2") (pintype "passive"))
      (node (ref "U33") (pin "2") (pinfunction "SW_2") (pintype "power_in"))
    )
    (net (code "151") (name "Net-(U33-VBST)") (class "Default")
      (node (ref "C154") (pin "1") (pinfunction "1_1") (pintype "passive"))
      (node (ref "U33") (pin "6") (pinfunction "VBST_6") (pintype "power_in"))
    )
    (net (code "152") (name "Net-(U33-VFB)") (class "Default")
      (node (ref "R55") (pin "1") (pinfunction "1_1") (pintype "passive"))
      (node (ref "R56") (pin "2") (pinfunction "2_2") (pintype "passive"))
      (node (ref "U33") (pin "4") (pinfunction "VFB_4") (pintype "input"))
    )
    (net (code "153") (name "Net-(U34-BIAS)") (class "Default")
      (node (ref "C161") (pin "1") (pinfunction "1_1") (pintype "passive"))
      (node (ref "U34") (pin "12") (pinfunction "BIAS_12") (pintype "input"))
    )
    (net (code "154") (name "Net-(U34-FB)") (class "Default")
      (node (ref "C160") (pin "2") (pinfunction "2_2") (pintype "passive"))
      (node (ref "R57") (pin "1") (pinfunction "1_1") (pintype "passive"))
      (node (ref "R58") (pin "2") (pinfunction "2_2") (pintype "passive"))
      (node (ref "U34") (pin "3") (pinfunction "FB_3") (pintype "input"))
    )
    (net (code "155") (name "Net-(U34-NR{slash}SS)") (class "Default")
      (node (ref "C162") (pin "1") (pinfunction "1_1") (pintype "passive"))
      (node (ref "U34") (pin "13") (pinfunction "NR/SS_13") (pintype "passive"))
    )
    (net (code "156") (name "Net-(U34-SNS)") (class "Default")
      (node (ref "C160") (pin "1") (pinfunction "1_1") (pintype "passive"))
      (node (ref "U34") (pin "2") (pinfunction "SNS_2") (pintype "input"))
    )
    (net (code "157") (name "unconnected-(U18-FC-Pad1)") (class "Default")
      (node (ref "U18") (pin "1") (pinfunction "FC_1") (pintype "passive"))
    )
    (net (code "158") (name "unconnected-(U18-OSC-Pad7)") (class "Default")
      (node (ref "U18") (pin "7") (pinfunction "OSC_7") (pintype "passive"))
    )
    (net (code "159") (name "unconnected-(U19-FC-Pad1)") (class "Default")
      (node (ref "U19") (pin "1") (pinfunction "FC_1") (pintype "passive"))
    )
    (net (code "160") (name "unconnected-(U19-OSC-Pad7)") (class "Default")
      (node (ref "U19") (pin "7") (pinfunction "OSC_7") (pintype "passive"))
    )
    (net (code "161") (name "unconnected-(U20-FC-Pad1)") (class "Default")
      (node (ref "U20") (pin "1") (pinfunction "FC_1") (pintype "passive"))
    )
    (net (code "162") (name "unconnected-(U20-OSC-Pad7)") (class "Default")
      (node (ref "U20") (pin "7") (pinfunction "OSC_7") (pintype "passive"))
    )
    (net (code "163") (name "unconnected-(U21-FC-Pad1)") (class "Default")
      (node (ref "U21") (pin "1") (pinfunction "FC_1") (pintype "passive"))
    )
    (net (code "164") (name "unconnected-(U21-OSC-Pad7)") (class "Default")
      (node (ref "U21") (pin "7") (pinfunction "OSC_7") (pintype "passive"))
    )
    (net (code "165") (name "unconnected-(U22-FC-Pad1)") (class "Default")
      (node (ref "U22") (pin "1") (pinfunction "FC_1") (pintype "passive"))
    )
    (net (code "166") (name "unconnected-(U22-OSC-Pad7)") (class "Default")
      (node (ref "U22") (pin "7") (pinfunction "OSC_7") (pintype "passive"))
    )
    (net (code "167") (name "unconnected-(U32-1.6V-Pad11)") (class "Default")
      (node (ref "U32") (pin "11") (pinfunction "1.6V_11") (pintype "input"))
    )
    (net (code "168") (name "unconnected-(U32-50MV-Pad5)") (class "Default")
      (node (ref "U32") (pin "5") (pinfunction "50MV_5") (pintype "input"))
    )
    (net (code "169") (name "unconnected-(U32-100MV-Pad6)") (class "Default")
      (node (ref "U32") (pin "6") (pinfunction "100MV_6") (pintype "input"))
    )
    (net (code "170") (name "unconnected-(U32-200MV-Pad7)") (class "Default")
      (node (ref "U32") (pin "7") (pinfunction "200MV_7") (pintype "input"))
    )
    (net (code "171") (name "unconnected-(U32-400MV-Pad9)") (class "Default")
      (node (ref "U32") (pin "9") (pinfunction "400MV_9") (pintype "input"))
    )
    (net (code "172") (name "unconnected-(U32-800MV-Pad10)") (class "Default")
      (node (ref "U32") (pin "10") (pinfunction "800MV_10") (pintype "input"))
    )
    (net (code "173") (name "unconnected-(U32-PG-Pad4)") (class "Default")
      (node (ref "U32") (pin "4") (pinfunction "PG_4") (pintype "output"))
    )
    (net (code "174") (name "unconnected-(U34-1.6V-Pad11)") (class "Default")
      (node (ref "U34") (pin "11") (pinfunction "1.6V_11") (pintype "input"))
    )
    (net (code "175") (name "unconnected-(U34-50MV-Pad5)") (class "Default")
      (node (ref "U34") (pin "5") (pinfunction "50MV_5") (pintype "input"))
    )
    (net (code "176") (name "unconnected-(U34-100MV-Pad6)") (class "Default")
      (node (ref "U34") (pin "6") (pinfunction "100MV_6") (pintype "input"))
    )
    (net (code "177") (name "unconnected-(U34-200MV-Pad7)") (class "Default")
      (node (ref "U34") (pin "7") (pinfunction "200MV_7") (pintype "input"))
    )
    (net (code "178") (name "unconnected-(U34-400MV-Pad9)") (class "Default")
      (node (ref "U34") (pin "9") (pinfunction "400MV_9") (pintype "input"))
    )
    (net (code "179") (name "unconnected-(U34-800MV-Pad10)") (class "Default")
      (node (ref "U34") (pin "10") (pinfunction "800MV_10") (pintype "input"))
    )
    (net (code "180") (name "unconnected-(U34-PG-Pad4)") (class "Default")
      (node (ref "U34") (pin "4") (pinfunction "PG_4") (pintype "output"))
    )
  )
)
